# DAC_STM32_Board_v5_-_AD5391.net
KiCad netlist of a schematic drawn in EAGLE
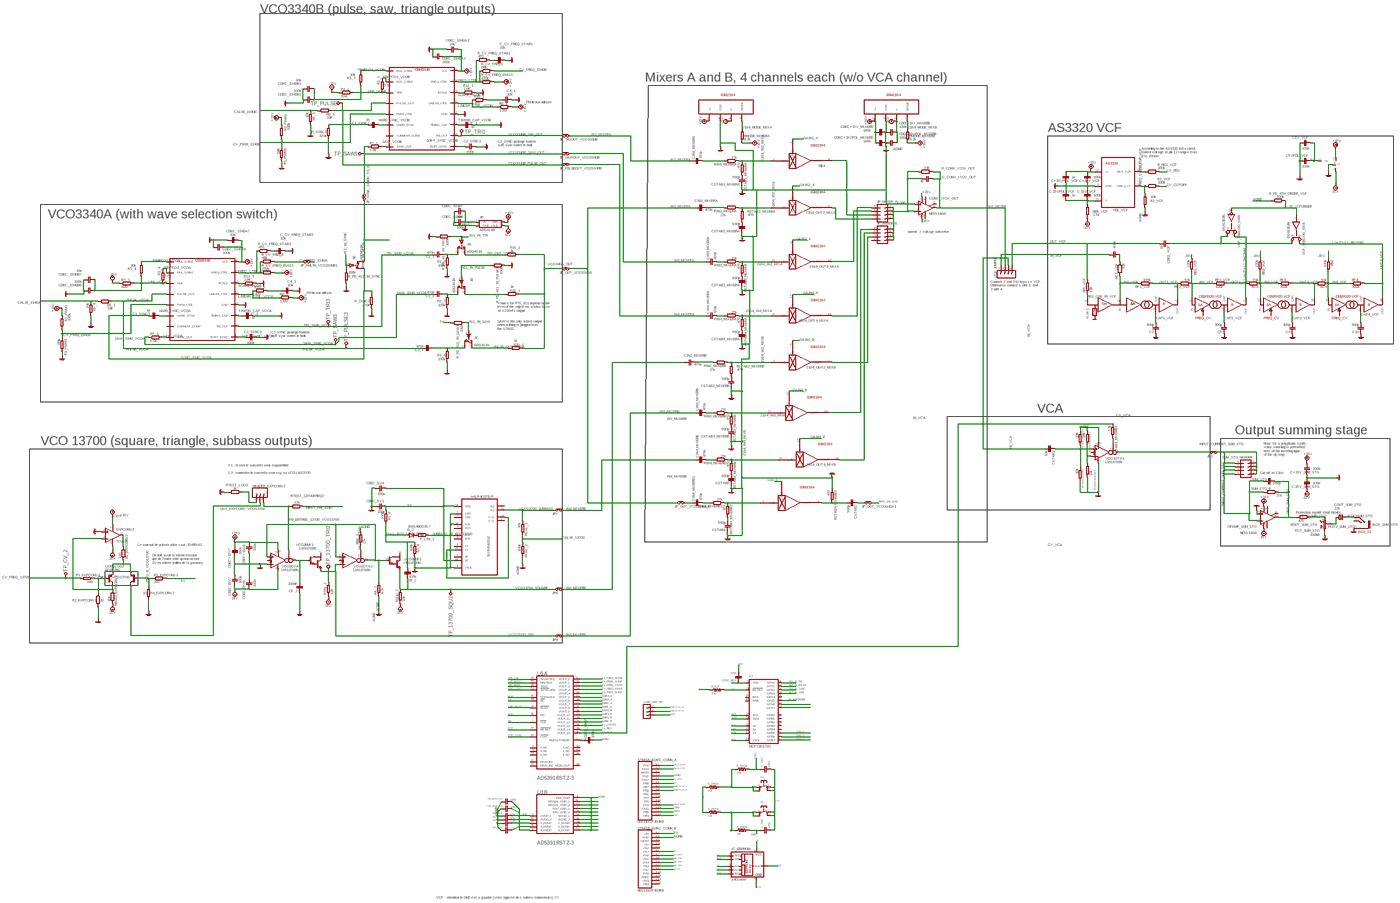
[diagram p0: schematic, sheet 1, overview]
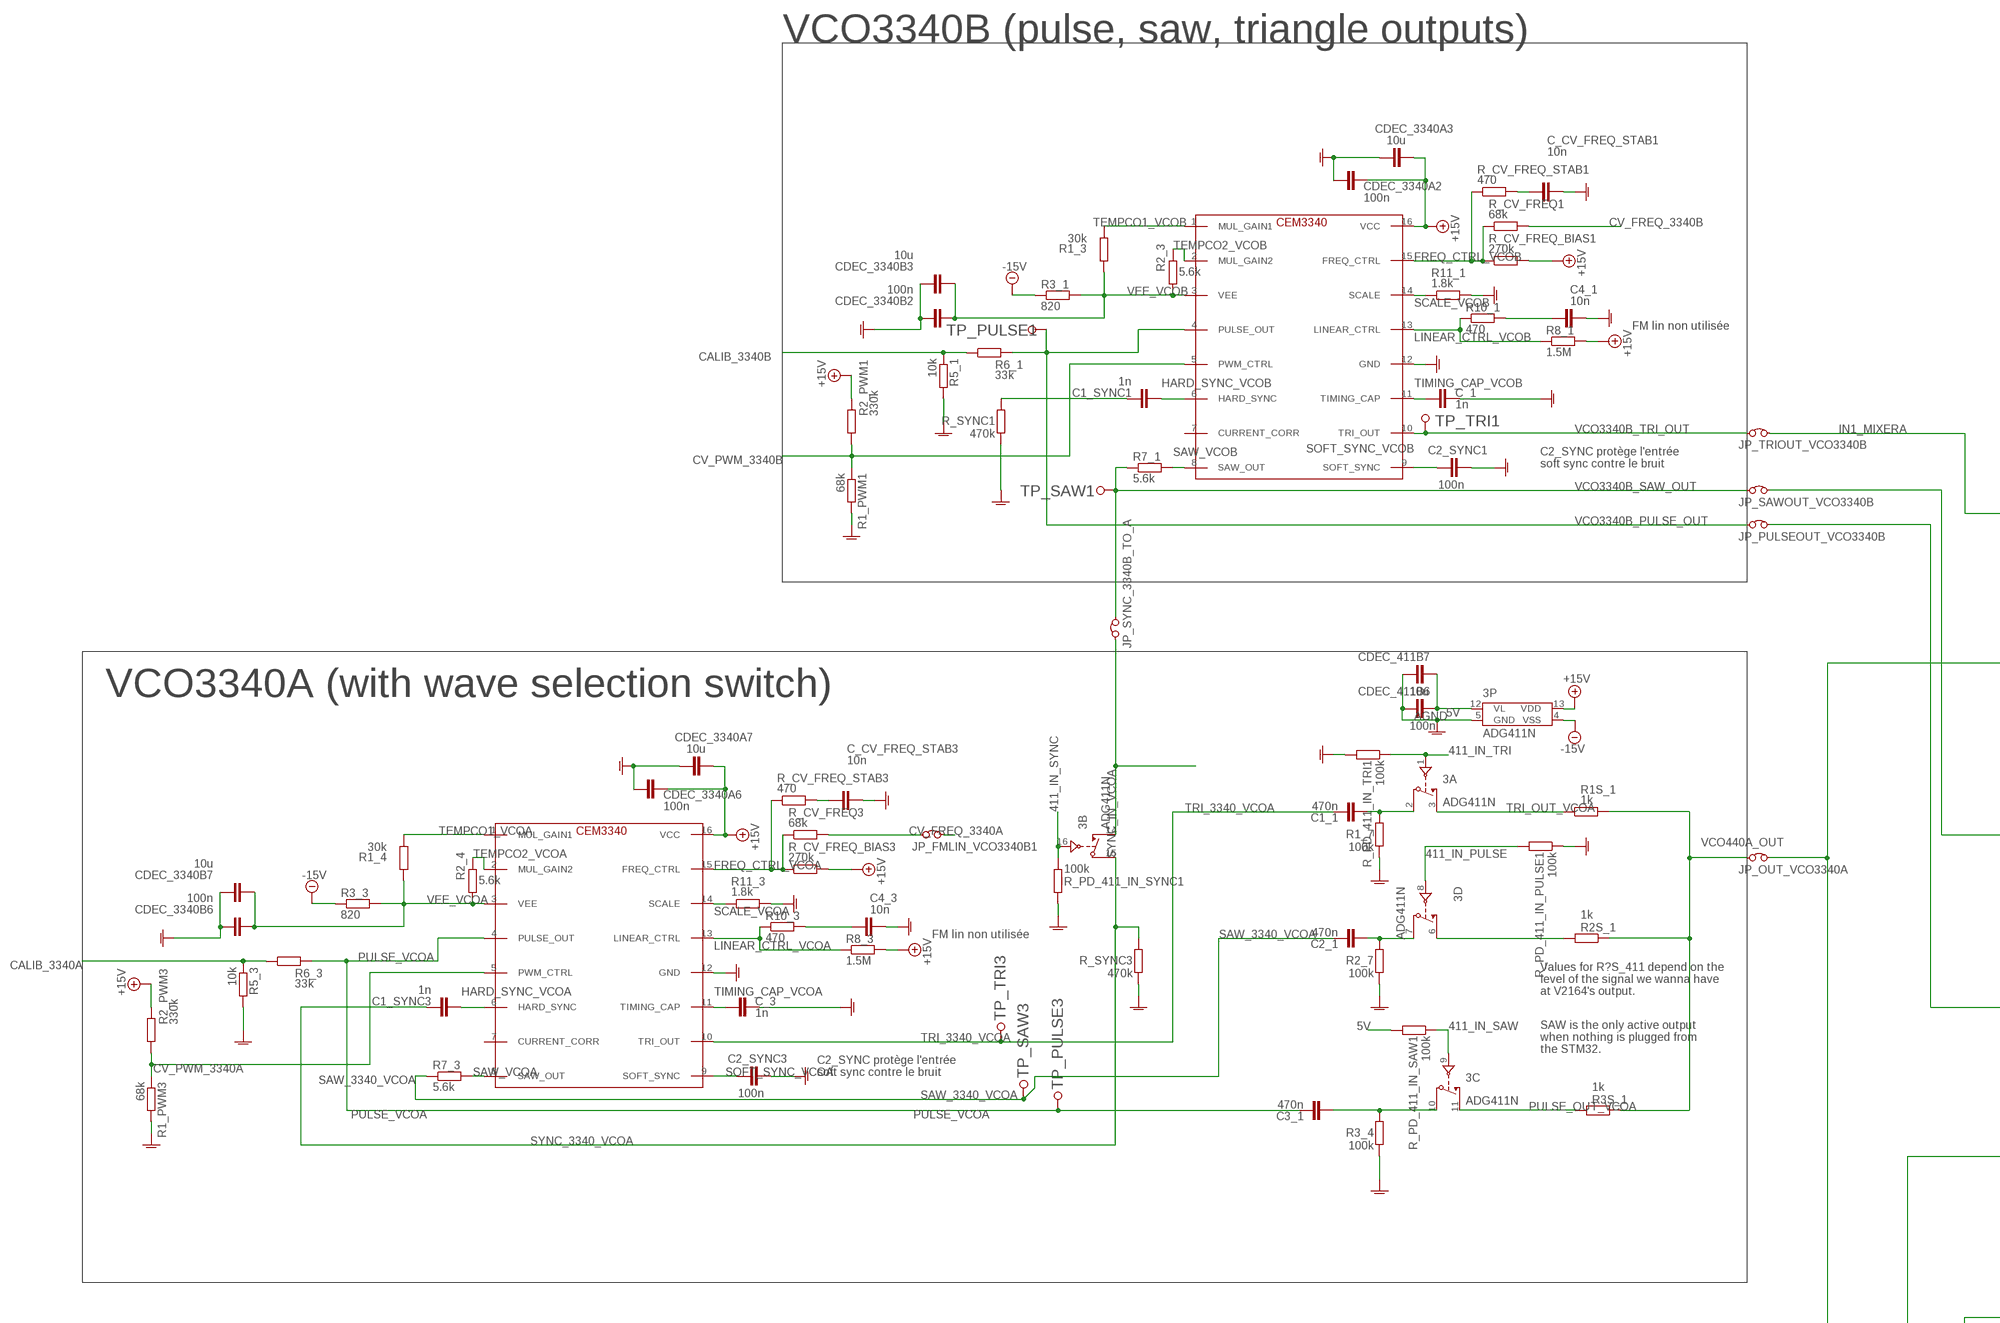
[diagram p1: schematic, sheet 1, part 1 of 5]
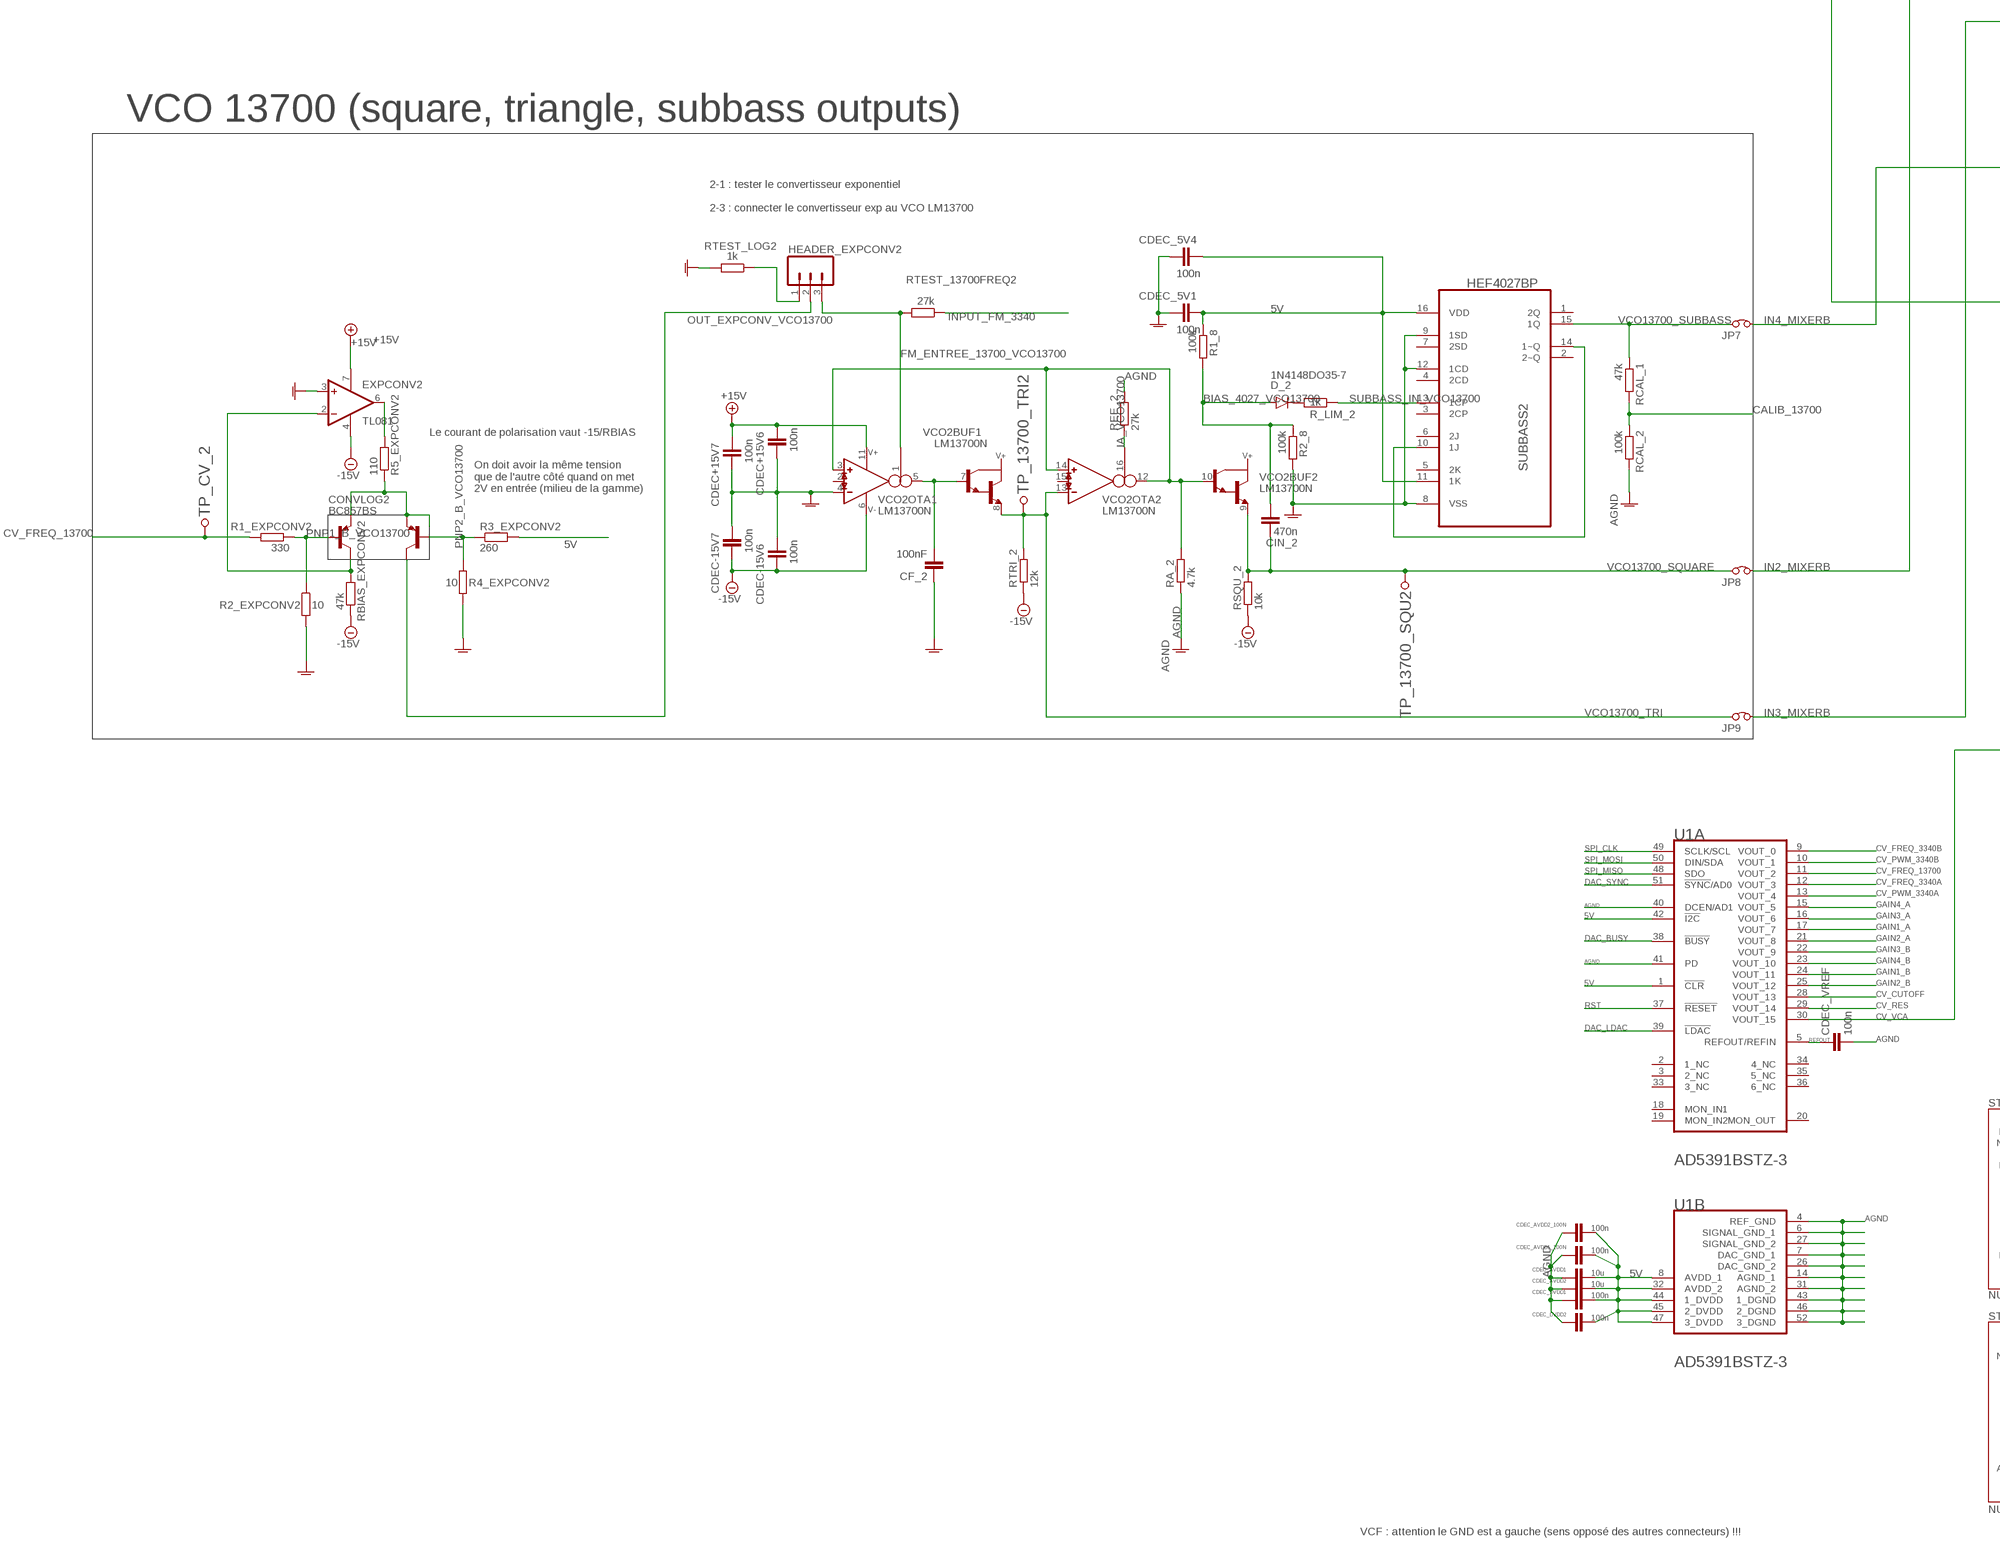
[diagram p2: schematic, sheet 1, part 2 of 5]
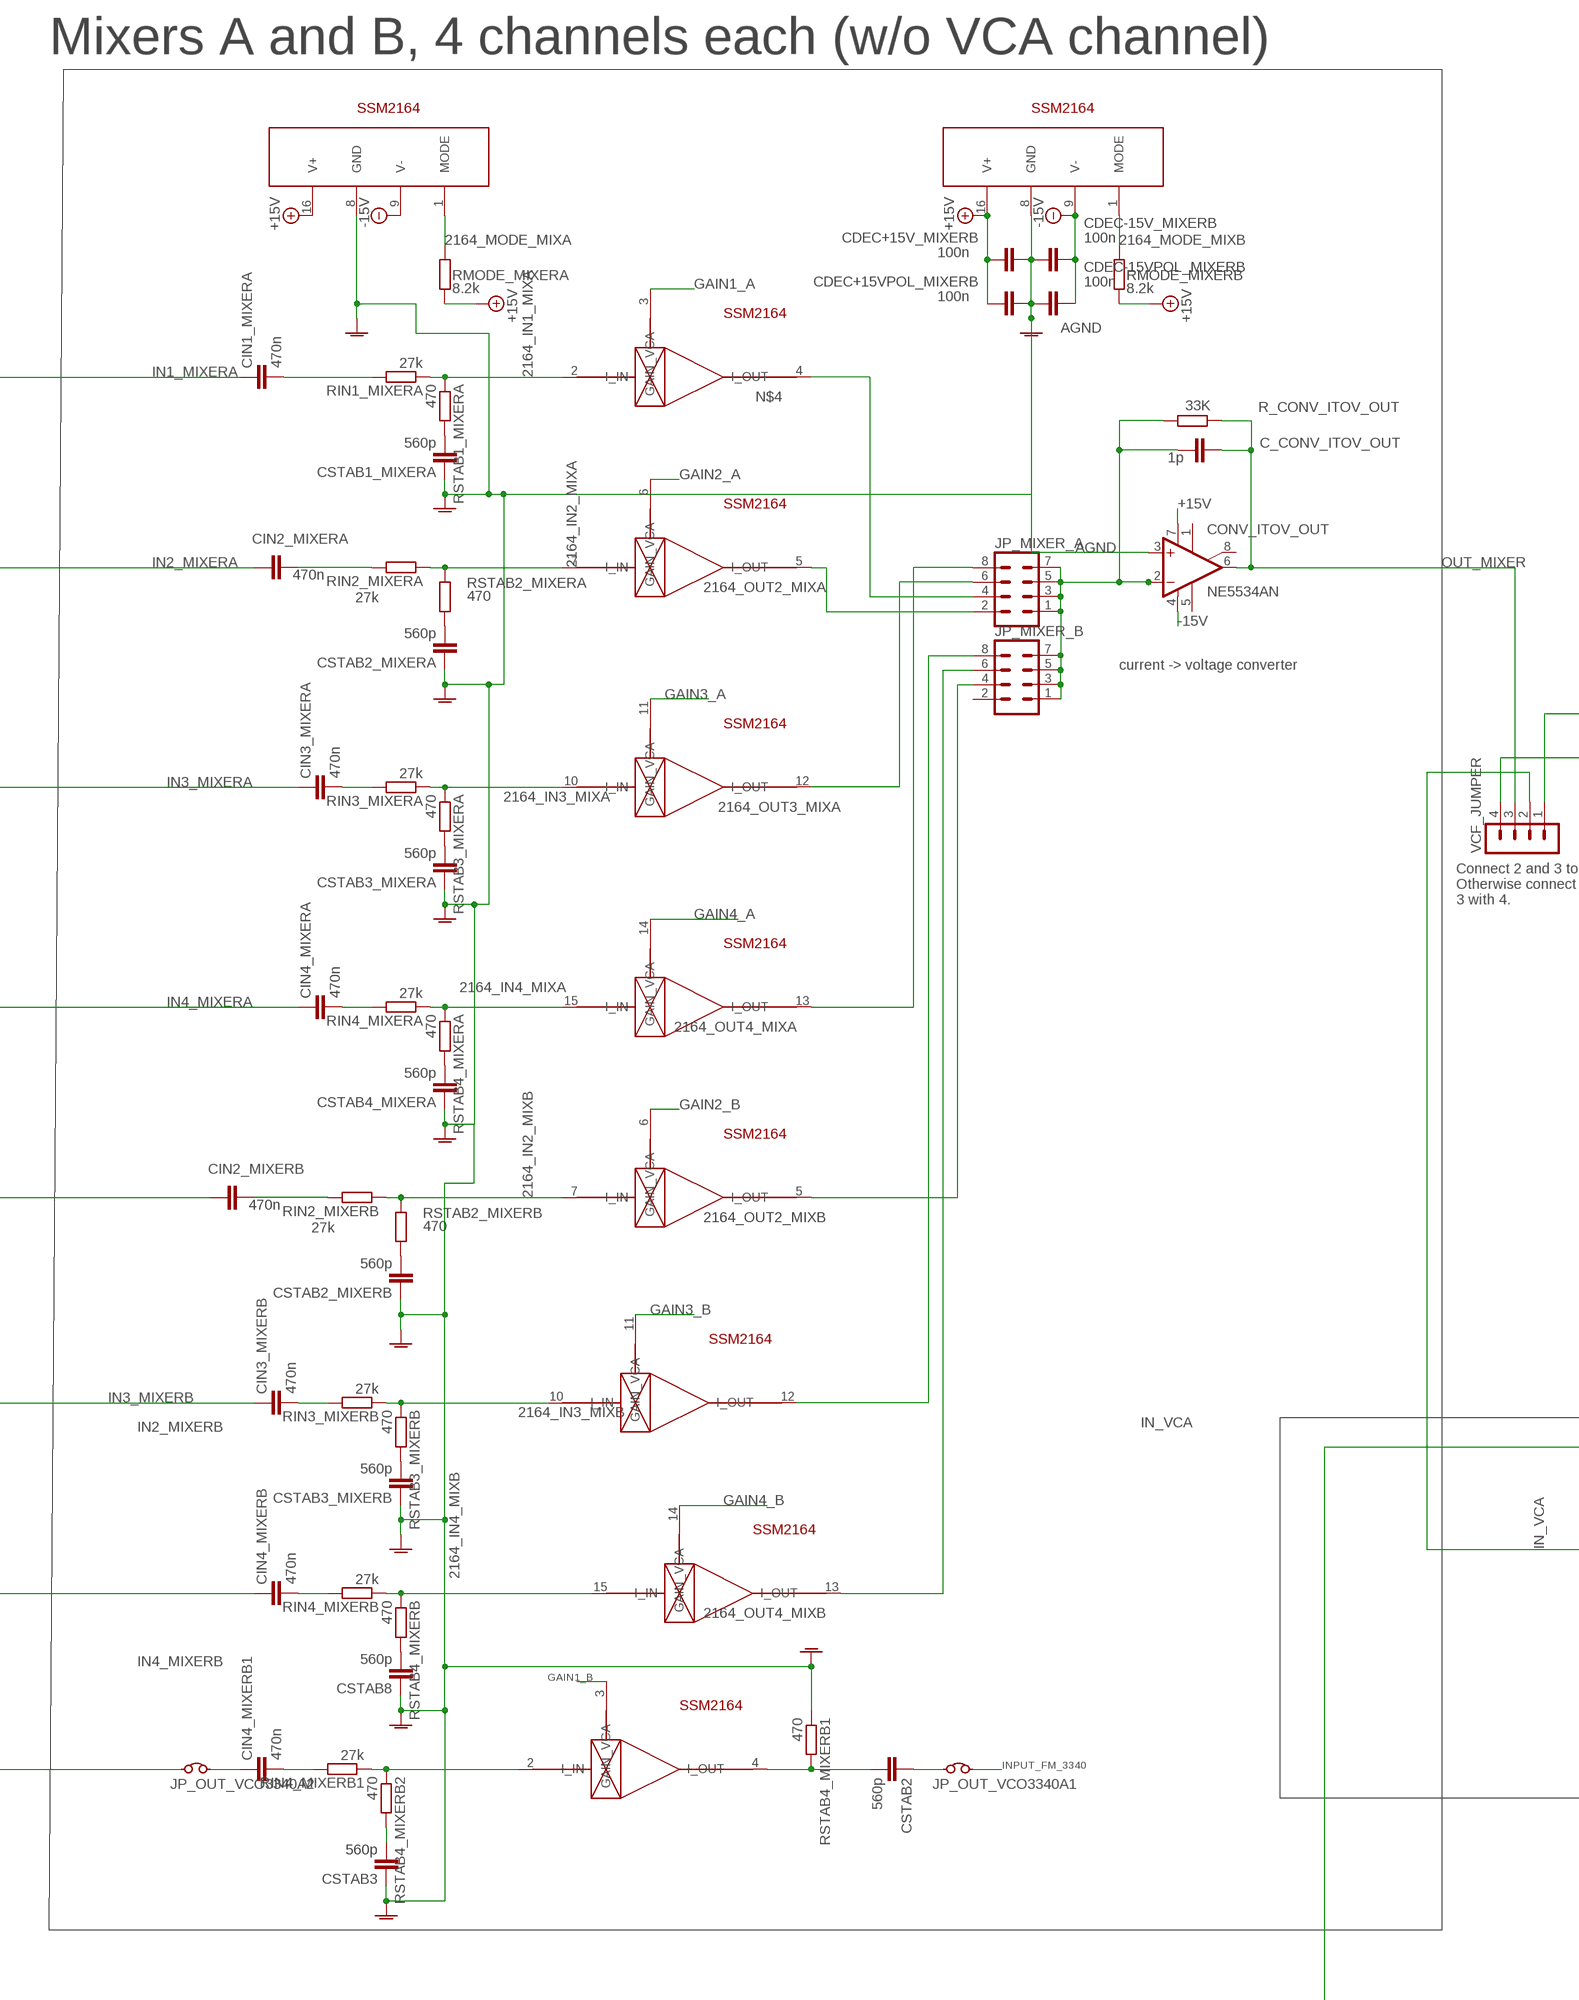
[diagram p3: schematic, sheet 1, part 3 of 5]
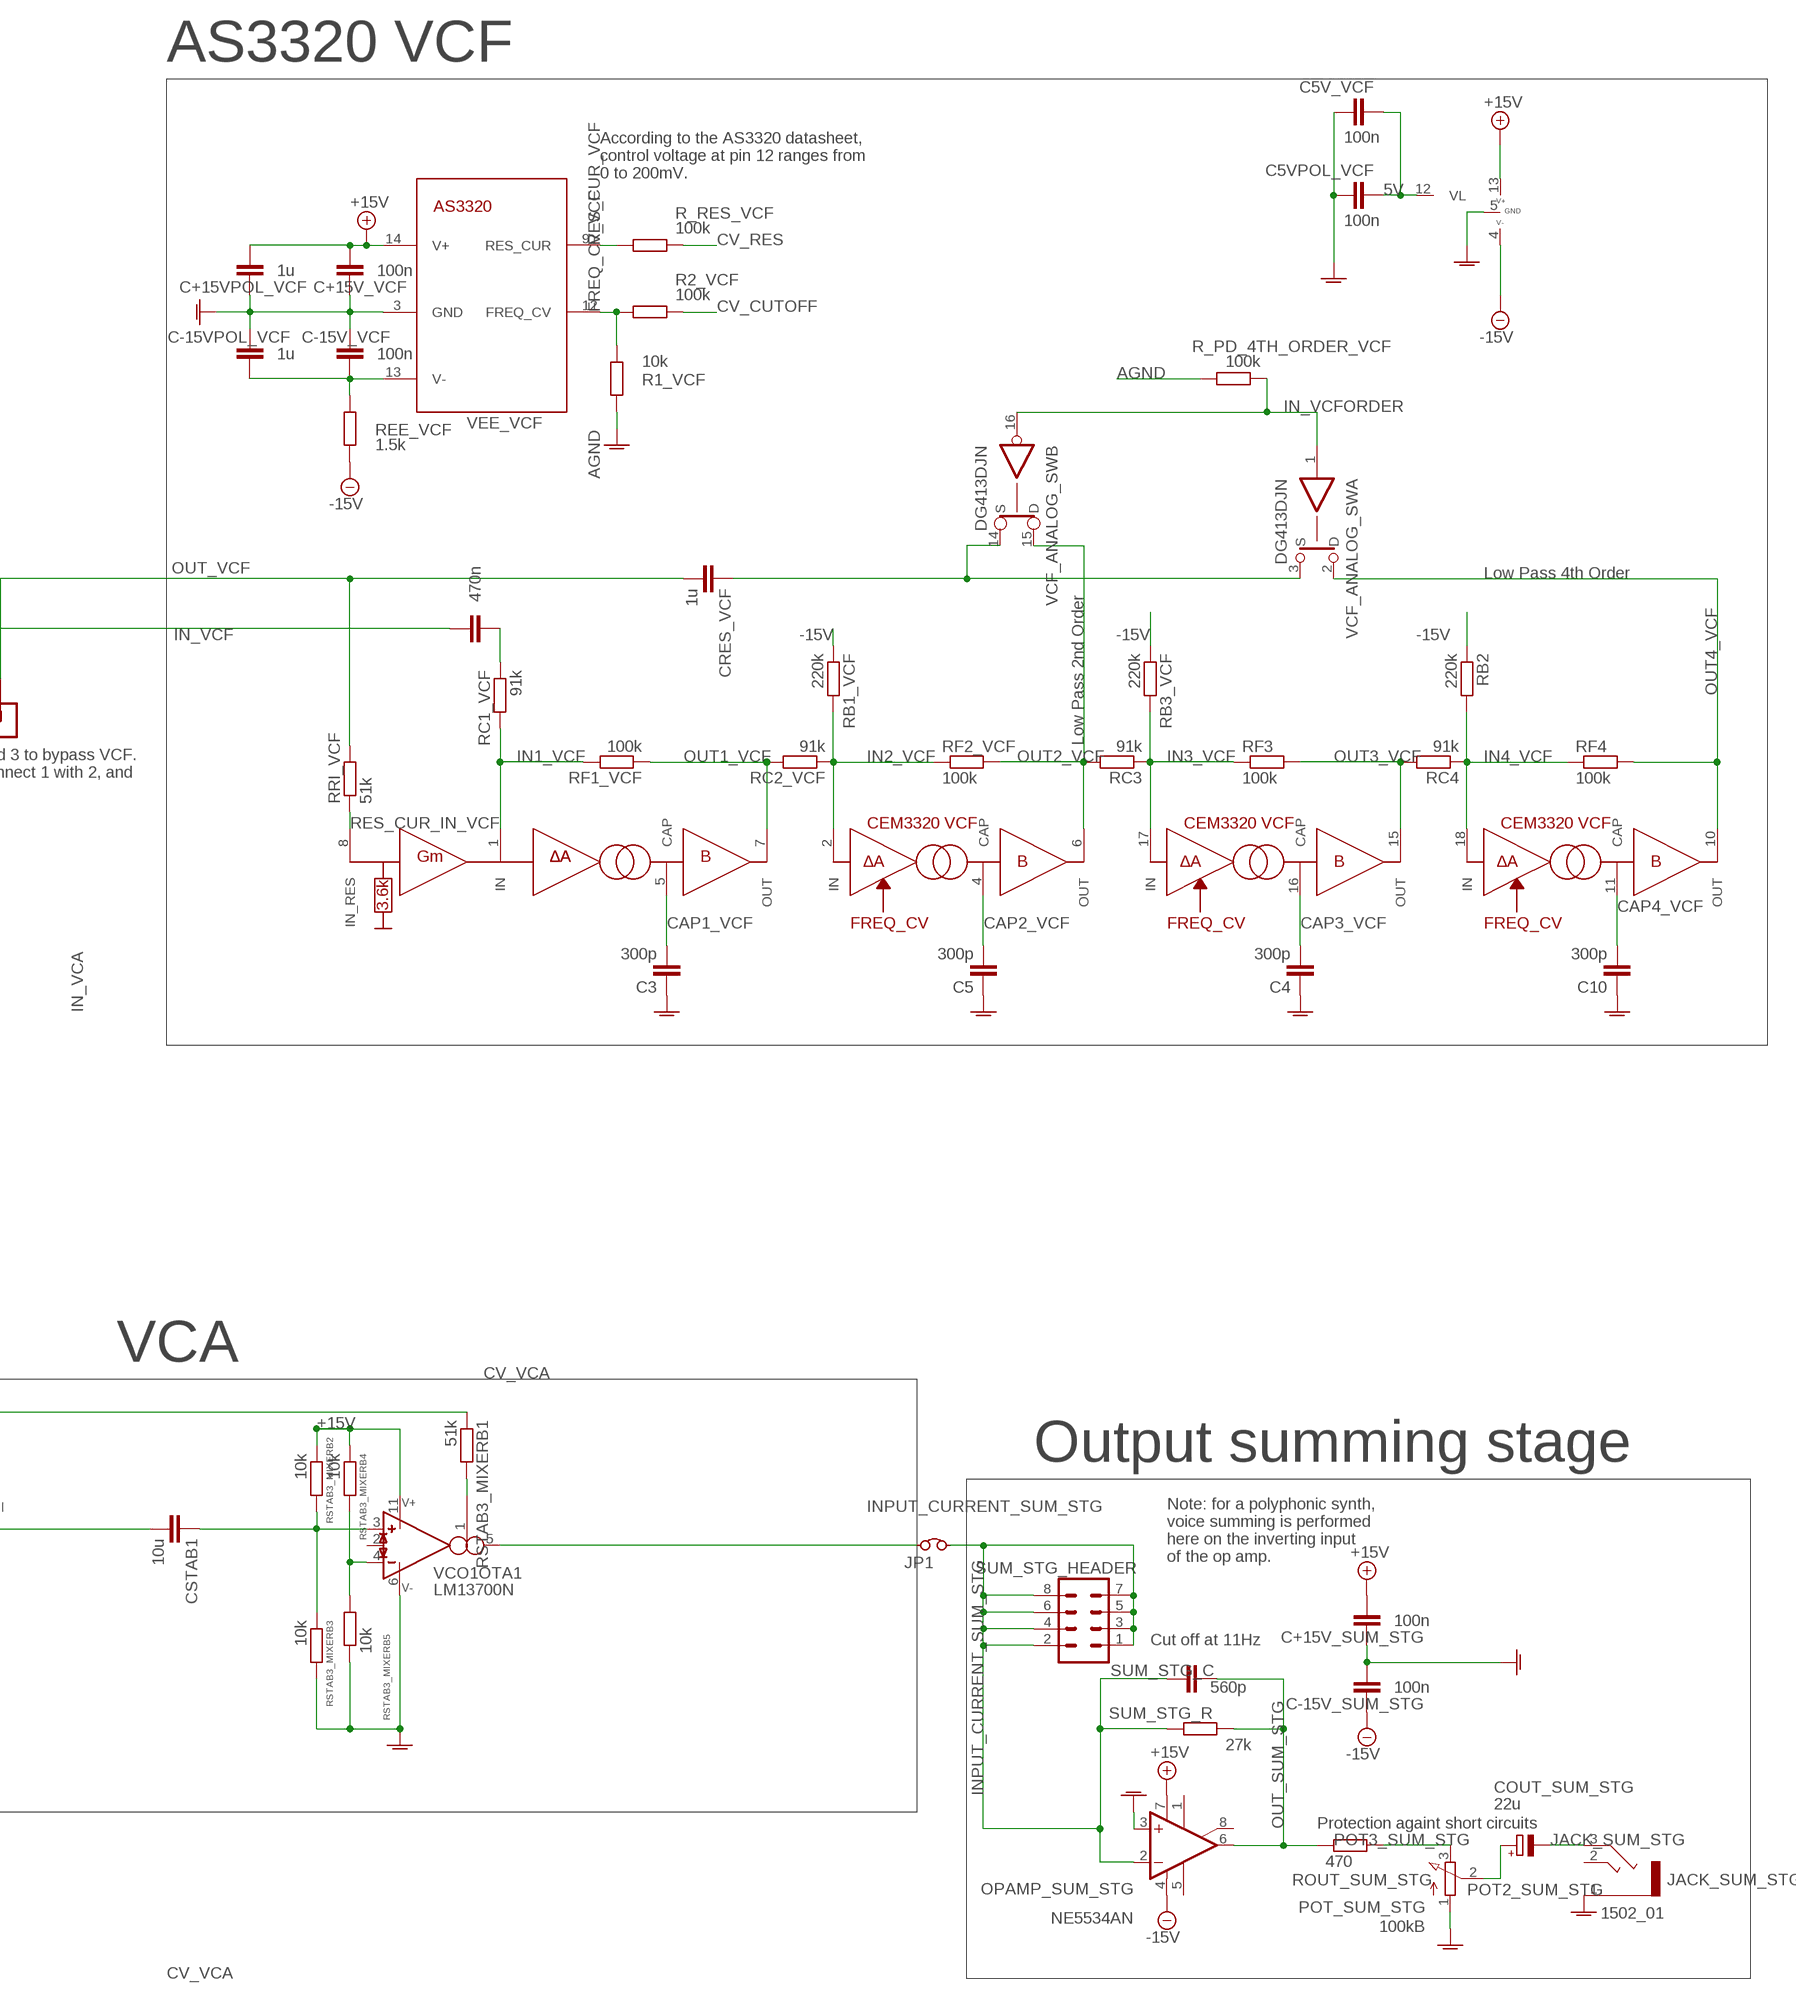
[diagram p4: schematic, sheet 1, part 4 of 5]
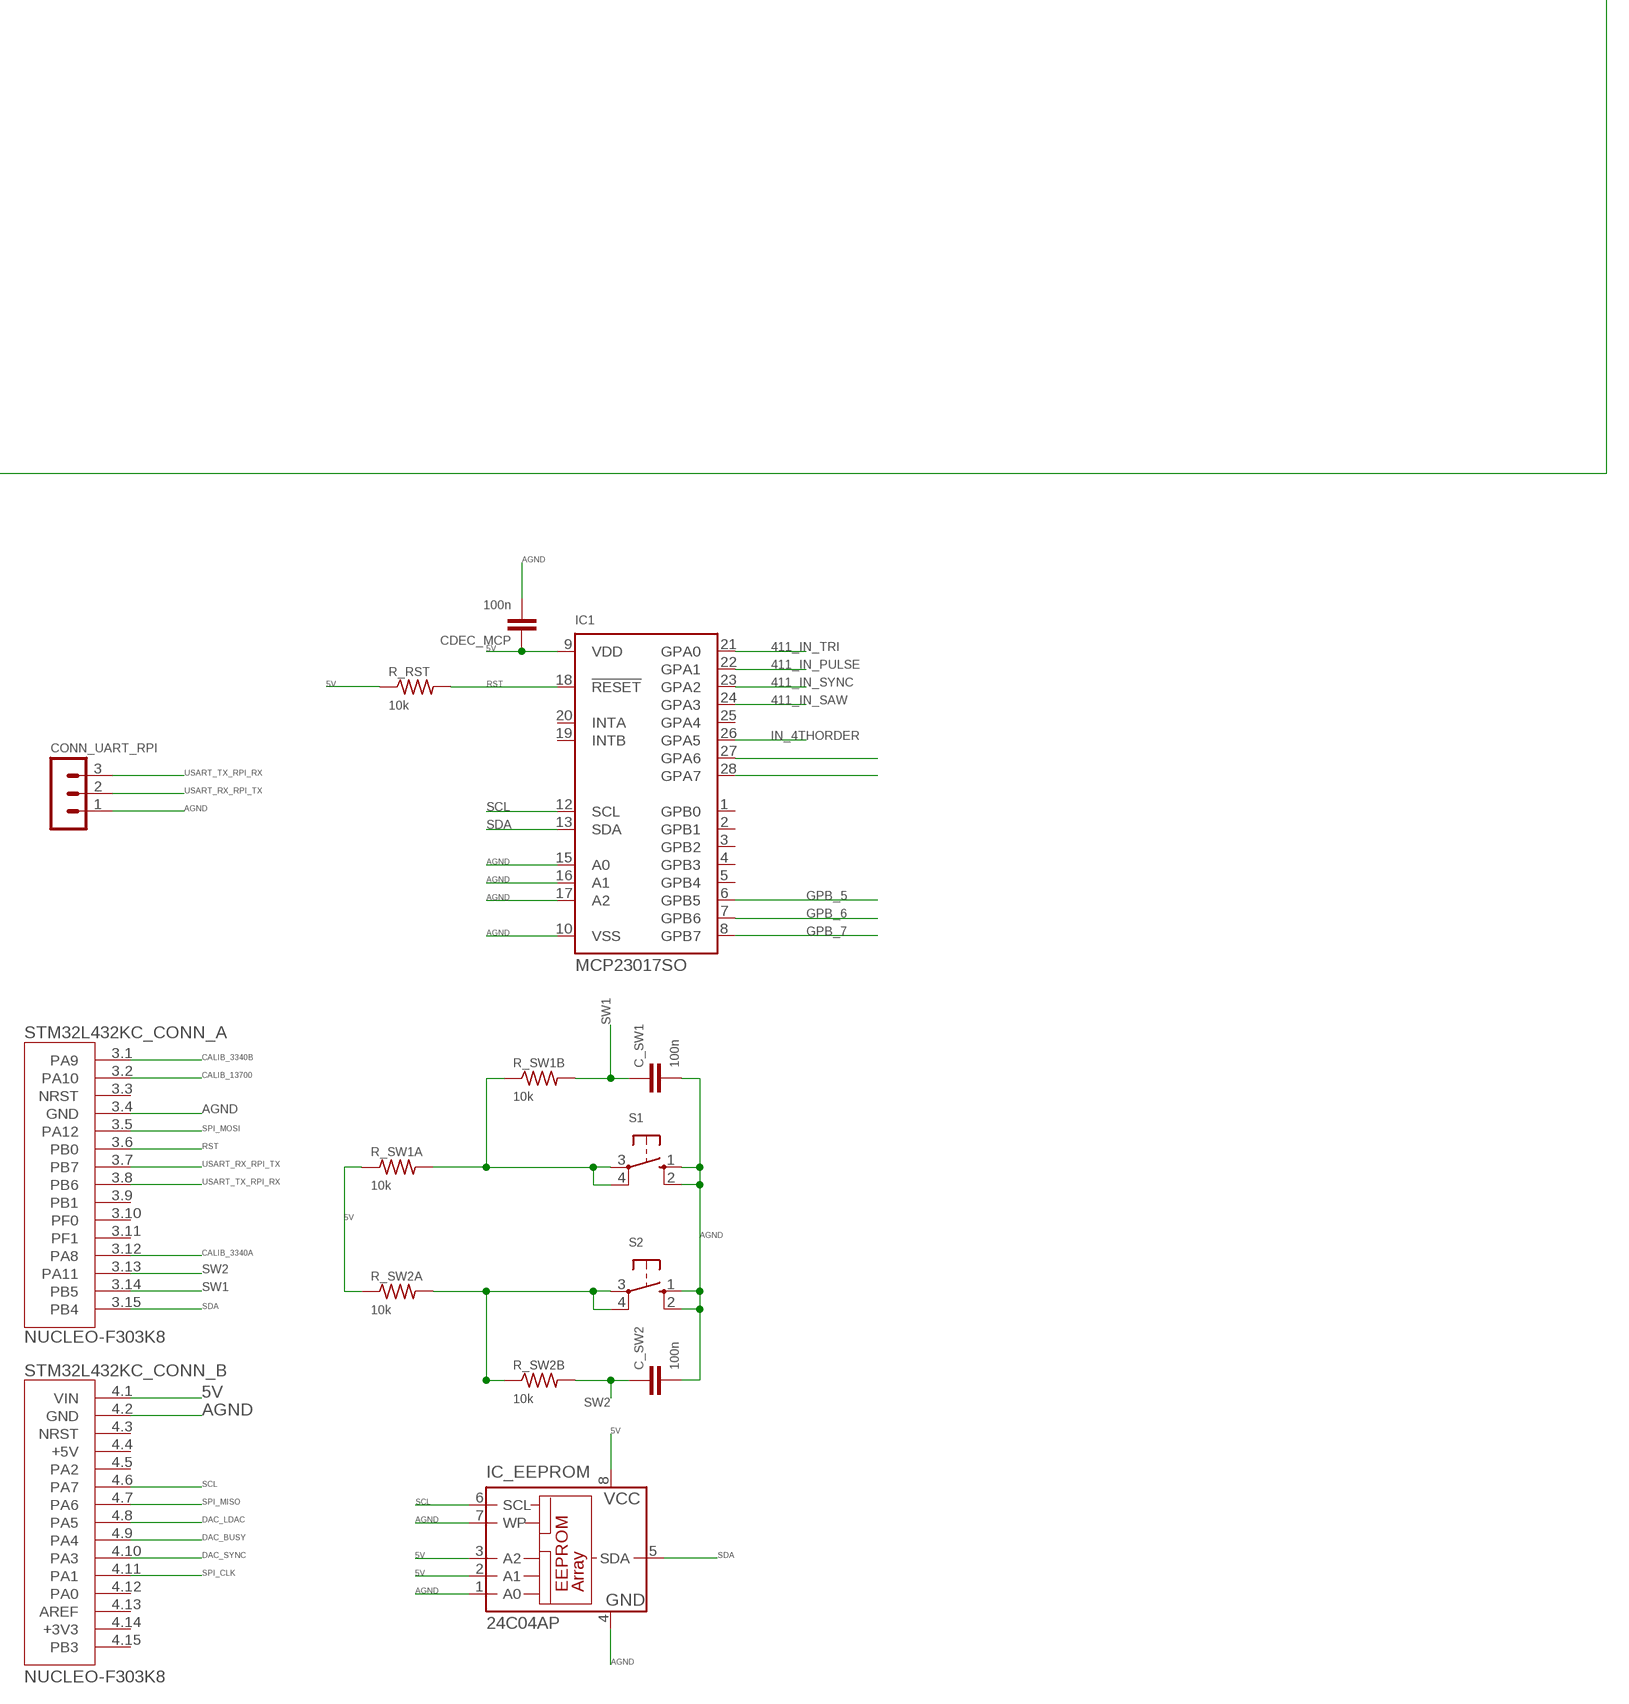
[diagram p5: schematic, sheet 1, part 5 of 5]

(export (version "E")
  (design (tool "Eeschema 10.0.6"))
  (components
    (comp (ref "3")
      (value "ADG411N")
      (footprint "eagle-import:DIL16")
      (fields (field (name "MF") "ALTERA CORPORATION") (field (name "MPN") "ADG411BN"))
      (libsource (lib "eagle-import") (part "ADG411N"))
    )
    (comp (ref "3340A")
      (value "CEM3340")
      (footprint "eagle-import:DIL16")
      (libsource (lib "eagle-import") (part "CEM3340"))
    )
    (comp (ref "3340B")
      (value "CEM3340")
      (footprint "eagle-import:DIL16")
      (libsource (lib "eagle-import") (part "CEM3340"))
    )
    (comp (ref "C+15VPOL_VCF")
      (value "1u")
      (footprint "eagle-import:C075-032X103")
      (libsource (lib "eagle-import") (part "rcl_334_C-EU075-032X103"))
    )
    (comp (ref "C+15V_SUM_STG")
      (value "100n")
      (footprint "eagle-import:C075-032X103")
      (libsource (lib "eagle-import") (part "rcl_334_C-EU075-032X103"))
    )
    (comp (ref "C+15V_VCF")
      (value "100n")
      (footprint "eagle-import:C075-032X103")
      (libsource (lib "eagle-import") (part "rcl_334_C-EU075-032X103"))
    )
    (comp (ref "C-15VPOL_VCF")
      (value "1u")
      (footprint "eagle-import:C075-032X103")
      (libsource (lib "eagle-import") (part "rcl_334_C-EU075-032X103"))
    )
    (comp (ref "C-15V_SUM_STG")
      (value "100n")
      (footprint "eagle-import:C075-032X103")
      (libsource (lib "eagle-import") (part "rcl_334_C-EU075-032X103"))
    )
    (comp (ref "C-15V_VCF")
      (value "100n")
      (footprint "eagle-import:C075-032X103")
      (libsource (lib "eagle-import") (part "rcl_334_C-EU075-032X103"))
    )
    (comp (ref "C1_1")
      (value "470n")
      (footprint "eagle-import:C075-032X103")
      (libsource (lib "eagle-import") (part "rcl_334_C-EU075-032X103"))
    )
    (comp (ref "C1_SYNC1")
      (value "1n")
      (footprint "eagle-import:C075-032X103")
      (libsource (lib "eagle-import") (part "rcl_334_C-EU075-032X103"))
    )
    (comp (ref "C1_SYNC3")
      (value "1n")
      (footprint "eagle-import:C075-032X103")
      (libsource (lib "eagle-import") (part "rcl_334_C-EU075-032X103"))
    )
    (comp (ref "C2_1")
      (value "470n")
      (footprint "eagle-import:C075-032X103")
      (libsource (lib "eagle-import") (part "rcl_334_C-EU075-032X103"))
    )
    (comp (ref "C2_SYNC1")
      (value "100n")
      (footprint "eagle-import:C075-032X103")
      (libsource (lib "eagle-import") (part "rcl_334_C-EU075-032X103"))
    )
    (comp (ref "C2_SYNC3")
      (value "100n")
      (footprint "eagle-import:C050-025X075")
      (libsource (lib "eagle-import") (part "rcl_334_C-EU050-025X075"))
    )
    (comp (ref "C3")
      (value "300p")
      (footprint "eagle-import:C075-032X103")
      (libsource (lib "eagle-import") (part "rcl_334_C-EU075-032X103"))
    )
    (comp (ref "C3_1")
      (value "470n")
      (footprint "eagle-import:C102-043X133")
      (libsource (lib "eagle-import") (part "rcl_334_C-EU102-043X133"))
    )
    (comp (ref "C4")
      (value "300p")
      (footprint "eagle-import:C075-032X103")
      (libsource (lib "eagle-import") (part "rcl_334_C-EU075-032X103"))
    )
    (comp (ref "C4_1")
      (value "10n")
      (footprint "eagle-import:C050-025X075")
      (libsource (lib "eagle-import") (part "rcl_334_C-EU050-025X075"))
    )
    (comp (ref "C4_3")
      (value "10n")
      (footprint "eagle-import:C050-025X075")
      (libsource (lib "eagle-import") (part "rcl_334_C-EU050-025X075"))
    )
    (comp (ref "C5")
      (value "300p")
      (footprint "eagle-import:C075-032X103")
      (libsource (lib "eagle-import") (part "rcl_334_C-EU075-032X103"))
    )
    (comp (ref "C5VPOL_VCF")
      (value "100n")
      (footprint "eagle-import:C075-032X103")
      (libsource (lib "eagle-import") (part "rcl_334_C-EU075-032X103"))
    )
    (comp (ref "C5V_VCF")
      (value "100n")
      (footprint "eagle-import:C075-032X103")
      (libsource (lib "eagle-import") (part "rcl_334_C-EU075-032X103"))
    )
    (comp (ref "C10")
      (value "300p")
      (footprint "eagle-import:C075-032X103")
      (libsource (lib "eagle-import") (part "rcl_334_C-EU075-032X103"))
    )
    (comp (ref "CDEC+15V6")
      (value "100n")
      (footprint "eagle-import:C075-032X103")
      (libsource (lib "eagle-import") (part "rcl_334_C-EU075-032X103"))
    )
    (comp (ref "CDEC+15V7")
      (value "100n")
      (footprint "eagle-import:C050-025X075")
      (libsource (lib "eagle-import") (part "rcl_334_C-EU050-025X075"))
    )
    (comp (ref "CDEC+15VPOL_MIXERB")
      (value "100n")
      (footprint "eagle-import:C075-032X103")
      (libsource (lib "eagle-import") (part "rcl_334_C-EU075-032X103"))
    )
    (comp (ref "CDEC+15V_MIXERB")
      (value "100n")
      (footprint "eagle-import:C050-030X075")
      (libsource (lib "eagle-import") (part "rcl_334_C-EU050-030X075"))
    )
    (comp (ref "CDEC-15V6")
      (value "100n")
      (footprint "eagle-import:C050-025X075")
      (libsource (lib "eagle-import") (part "rcl_334_C-EU050-025X075"))
    )
    (comp (ref "CDEC-15V7")
      (value "100n")
      (footprint "eagle-import:C075-032X103")
      (libsource (lib "eagle-import") (part "rcl_334_C-EU075-032X103"))
    )
    (comp (ref "CDEC-15VPOL_MIXERB")
      (value "100n")
      (footprint "eagle-import:C050-030X075")
      (libsource (lib "eagle-import") (part "rcl_334_C-EU050-030X075"))
    )
    (comp (ref "CDEC-15V_MIXERB")
      (value "100n")
      (footprint "eagle-import:C050-030X075")
      (libsource (lib "eagle-import") (part "rcl_334_C-EU050-030X075"))
    )
    (comp (ref "CDEC_5V1")
      (value "100n")
      (footprint "eagle-import:C050-025X075")
      (libsource (lib "eagle-import") (part "rcl_334_C-EU050-025X075"))
    )
    (comp (ref "CDEC_5V4")
      (value "100n")
      (footprint "eagle-import:C050-025X075")
      (libsource (lib "eagle-import") (part "rcl_334_C-EU050-025X075"))
    )
    (comp (ref "CDEC_411B6")
      (value "100n")
      (footprint "eagle-import:C050-025X075")
      (libsource (lib "eagle-import") (part "rcl_334_C-EU050-025X075"))
    )
    (comp (ref "CDEC_411B7")
      (value "10u")
      (footprint "eagle-import:C050-025X075")
      (libsource (lib "eagle-import") (part "rcl_334_C-EU050-025X075"))
    )
    (comp (ref "CDEC_3340A2")
      (value "100n")
      (footprint "eagle-import:C050-025X075")
      (libsource (lib "eagle-import") (part "rcl_334_C-EU050-025X075"))
    )
    (comp (ref "CDEC_3340A3")
      (value "10u")
      (footprint "eagle-import:C075-032X103")
      (libsource (lib "eagle-import") (part "rcl_334_C-EU075-032X103"))
    )
    (comp (ref "CDEC_3340A6")
      (value "100n")
      (footprint "eagle-import:C050-025X075")
      (libsource (lib "eagle-import") (part "rcl_334_C-EU050-025X075"))
    )
    (comp (ref "CDEC_3340A7")
      (value "10u")
      (footprint "eagle-import:C050-025X075")
      (libsource (lib "eagle-import") (part "rcl_334_C-EU050-025X075"))
    )
    (comp (ref "CDEC_3340B2")
      (value "100n")
      (footprint "eagle-import:C050-025X075")
      (libsource (lib "eagle-import") (part "rcl_334_C-EU050-025X075"))
    )
    (comp (ref "CDEC_3340B3")
      (value "10u")
      (footprint "eagle-import:C050-025X075")
      (libsource (lib "eagle-import") (part "rcl_334_C-EU050-025X075"))
    )
    (comp (ref "CDEC_3340B6")
      (value "100n")
      (footprint "eagle-import:C050-025X075")
      (libsource (lib "eagle-import") (part "rcl_334_C-EU050-025X075"))
    )
    (comp (ref "CDEC_3340B7")
      (value "10u")
      (footprint "eagle-import:C050-025X075")
      (libsource (lib "eagle-import") (part "rcl_334_C-EU050-025X075"))
    )
    (comp (ref "CDEC_AVDD1")
      (value "10u")
      (footprint "eagle-import:C050-030X075")
      (libsource (lib "eagle-import") (part "C-EU050-030X075"))
    )
    (comp (ref "CDEC_AVDD1_100N")
      (value "100n")
      (footprint "eagle-import:C050-030X075")
      (libsource (lib "eagle-import") (part "C-EU050-030X075"))
    )
    (comp (ref "CDEC_AVDD2")
      (value "10u")
      (footprint "eagle-import:C050-030X075")
      (libsource (lib "eagle-import") (part "C-EU050-030X075"))
    )
    (comp (ref "CDEC_AVDD2_100N")
      (value "100n")
      (footprint "eagle-import:C050-030X075")
      (libsource (lib "eagle-import") (part "C-EU050-030X075"))
    )
    (comp (ref "CDEC_DVDD1")
      (value "100n")
      (footprint "eagle-import:C075-032X103")
      (libsource (lib "eagle-import") (part "C-EU075-032X103"))
    )
    (comp (ref "CDEC_DVDD2")
      (value "100n")
      (footprint "eagle-import:C050-030X075")
      (libsource (lib "eagle-import") (part "C-EU050-030X075"))
    )
    (comp (ref "CDEC_MCP")
      (value "100n")
      (footprint "eagle-import:C075-032X103")
      (libsource (lib "eagle-import") (part "C-EU075-032X103"))
    )
    (comp (ref "CDEC_VREF")
      (value "100n")
      (footprint "eagle-import:C050-030X075")
      (libsource (lib "eagle-import") (part "C-EU050-030X075"))
    )
    (comp (ref "CF_2")
      (value "100nF")
      (footprint "eagle-import:C050-025X075")
      (libsource (lib "eagle-import") (part "rcl_334_C-EU050-025X075"))
    )
    (comp (ref "CIN1_MIXERA")
      (value "470n")
      (footprint "eagle-import:C050-030X075")
      (fields (field (name "C3") "0.47 micro"))
      (libsource (lib "eagle-import") (part "rcl_334_C-EU050-030X075"))
    )
    (comp (ref "CIN2_MIXERA")
      (value "470n")
      (footprint "eagle-import:C050-030X075")
      (fields (field (name "C3") "0.47 micro"))
      (libsource (lib "eagle-import") (part "rcl_334_C-EU050-030X075"))
    )
    (comp (ref "CIN2_MIXERB")
      (value "470n")
      (footprint "eagle-import:C050-030X075")
      (fields (field (name "C3") "0.47 micro"))
      (libsource (lib "eagle-import") (part "rcl_334_C-EU050-030X075"))
    )
    (comp (ref "CIN3_MIXERA")
      (value "470n")
      (footprint "eagle-import:C050-030X075")
      (fields (field (name "C3") "0.47 micro"))
      (libsource (lib "eagle-import") (part "rcl_334_C-EU050-030X075"))
    )
    (comp (ref "CIN3_MIXERB")
      (value "470n")
      (footprint "eagle-import:C050-030X075")
      (fields (field (name "C3") "0.47 micro"))
      (libsource (lib "eagle-import") (part "rcl_334_C-EU050-030X075"))
    )
    (comp (ref "CIN4_MIXERA")
      (value "470n")
      (footprint "eagle-import:C050-030X075")
      (fields (field (name "C3") "0.47 micro"))
      (libsource (lib "eagle-import") (part "rcl_334_C-EU050-030X075"))
    )
    (comp (ref "CIN4_MIXERB")
      (value "470n")
      (footprint "eagle-import:C050-030X075")
      (fields (field (name "C3") "0.47 micro"))
      (libsource (lib "eagle-import") (part "rcl_334_C-EU050-030X075"))
    )
    (comp (ref "CIN4_MIXERB1")
      (value "470n")
      (footprint "eagle-import:C050-030X075")
      (fields (field (name "C3") "0.47 micro"))
      (libsource (lib "eagle-import") (part "rcl_334_C-EU050-030X075"))
    )
    (comp (ref "CIN_2")
      (value "470n")
      (footprint "eagle-import:C050-025X075")
      (libsource (lib "eagle-import") (part "rcl_334_C-EU050-025X075"))
    )
    (comp (ref "CONN_UART_RPI")
      (value "MA03-1")
      (footprint "eagle-import:MA03-1")
      (libsource (lib "eagle-import") (part "MA03-1"))
    )
    (comp (ref "CONVLOG2")
      (value "BC857BS")
      (footprint "eagle-import:DIL06")
      (libsource (lib "eagle-import") (part "BC857BS"))
    )
    (comp (ref "CONV_ITOV_OUT")
      (value "NE5534AN")
      (footprint "eagle-import:DIL08")
      (libsource (lib "eagle-import") (part "linear_262_NE5534NA"))
    )
    (comp (ref "COUT_SUM_STG")
      (value "22u")
      (footprint "eagle-import:B45181A")
      (libsource (lib "eagle-import") (part "CPOL-EUB45181A"))
    )
    (comp (ref "CRES_VCF")
      (value "1u")
      (footprint "eagle-import:C075-032X103")
      (libsource (lib "eagle-import") (part "rcl_334_C-EU075-032X103"))
    )
    (comp (ref "CSTAB1")
      (value "10u")
      (footprint "eagle-import:C050-030X075")
      (libsource (lib "eagle-import") (part "rcl_334_C-EU050-030X075"))
    )
    (comp (ref "CSTAB1_MIXERA")
      (value "560p")
      (footprint "eagle-import:C050-030X075")
      (libsource (lib "eagle-import") (part "rcl_334_C-EU050-030X075"))
    )
    (comp (ref "CSTAB2")
      (value "560p")
      (footprint "eagle-import:C050-030X075")
      (libsource (lib "eagle-import") (part "rcl_334_C-EU050-030X075"))
    )
    (comp (ref "CSTAB2_MIXERA")
      (value "560p")
      (footprint "eagle-import:C050-030X075")
      (libsource (lib "eagle-import") (part "rcl_334_C-EU050-030X075"))
    )
    (comp (ref "CSTAB2_MIXERB")
      (value "560p")
      (footprint "eagle-import:C050-030X075")
      (libsource (lib "eagle-import") (part "rcl_334_C-EU050-030X075"))
    )
    (comp (ref "CSTAB3")
      (value "560p")
      (footprint "eagle-import:C050-030X075")
      (libsource (lib "eagle-import") (part "rcl_334_C-EU050-030X075"))
    )
    (comp (ref "CSTAB3_MIXERA")
      (value "560p")
      (footprint "eagle-import:C050-030X075")
      (libsource (lib "eagle-import") (part "rcl_334_C-EU050-030X075"))
    )
    (comp (ref "CSTAB3_MIXERB")
      (value "560p")
      (footprint "eagle-import:C050-030X075")
      (libsource (lib "eagle-import") (part "rcl_334_C-EU050-030X075"))
    )
    (comp (ref "CSTAB4_MIXERA")
      (value "560p")
      (footprint "eagle-import:C050-030X075")
      (libsource (lib "eagle-import") (part "rcl_334_C-EU050-030X075"))
    )
    (comp (ref "CSTAB8")
      (value "560p")
      (footprint "eagle-import:C050-030X075")
      (libsource (lib "eagle-import") (part "rcl_334_C-EU050-030X075"))
    )
    (comp (ref "C_1")
      (value "1n")
      (footprint "eagle-import:C050-025X075")
      (libsource (lib "eagle-import") (part "rcl_334_C-EU050-025X075"))
    )
    (comp (ref "C_3")
      (value "1n")
      (footprint "eagle-import:C050-025X075")
      (libsource (lib "eagle-import") (part "rcl_334_C-EU050-025X075"))
    )
    (comp (ref "C_CONV_ITOV_OUT")
      (value "1p")
      (footprint "eagle-import:C050-030X075")
      (fields (field (name "C3") "0.47 micro"))
      (libsource (lib "eagle-import") (part "rcl_334_C-EU050-030X075"))
    )
    (comp (ref "C_CV_FREQ_STAB1")
      (value "10n")
      (footprint "eagle-import:C075-032X103")
      (libsource (lib "eagle-import") (part "rcl_334_C-EU075-032X103"))
    )
    (comp (ref "C_CV_FREQ_STAB3")
      (value "10n")
      (footprint "eagle-import:C075-032X103")
      (libsource (lib "eagle-import") (part "rcl_334_C-EU075-032X103"))
    )
    (comp (ref "C_IN2")
      (value "470n")
      (footprint "eagle-import:C050-025X075")
      (libsource (lib "eagle-import") (part "rcl_334_C-EU050-025X075"))
    )
    (comp (ref "C_SW1")
      (value "100n")
      (footprint "eagle-import:C050-030X075")
      (libsource (lib "eagle-import") (part "C-EU050-030X075"))
    )
    (comp (ref "C_SW2")
      (value "100n")
      (footprint "eagle-import:C050-030X075")
      (libsource (lib "eagle-import") (part "C-EU050-030X075"))
    )
    (comp (ref "D_2")
      (value "1N4148DO35-7")
      (footprint "eagle-import:DO35-7")
      (libsource (lib "eagle-import") (part "1N4148DO35-7"))
    )
    (comp (ref "EXPCONV2")
      (value "TL081")
      (footprint "eagle-import:DIL08")
      (libsource (lib "eagle-import") (part "1AMP_P7+4N"))
    )
    (comp (ref "HEADER_EXPCONV2")
      (value "M03")
      (footprint "eagle-import:03P")
      (libsource (lib "eagle-import") (part "M03"))
    )
    (comp (ref "IC1")
      (value "MCP23017SO")
      (footprint "eagle-import:SO28W")
      (fields (field (name "MF") "MICROCHIP") (field (name "MPN") "MCP23017-E/SO"))
      (libsource (lib "eagle-import") (part "MCP23017SO"))
    )
    (comp (ref "IC_EEPROM")
      (value "24C04AP")
      (footprint "eagle-import:DIL8")
      (fields (field (name "MPN") "AT24C04B-PU"))
      (libsource (lib "eagle-import") (part "24CP04A"))
    )
    (comp (ref "JACK_SUM_STG")
      (value "1502_01")
      (footprint "eagle-import:1502_01")
      (libsource (lib "eagle-import") (part "1502_01"))
    )
    (comp (ref "JP1")
      (value "JUMPER")
      (footprint "eagle-import:HDR2X1")
      (libsource (lib "eagle-import") (part "JUMPER"))
    )
    (comp (ref "JP7")
      (value "JUMPER")
      (footprint "eagle-import:HDR2X1")
      (libsource (lib "eagle-import") (part "JUMPER"))
    )
    (comp (ref "JP8")
      (value "JUMPER")
      (footprint "eagle-import:HDR2X1")
      (libsource (lib "eagle-import") (part "JUMPER"))
    )
    (comp (ref "JP9")
      (value "JUMPER")
      (footprint "eagle-import:HDR2X1")
      (libsource (lib "eagle-import") (part "JUMPER"))
    )
    (comp (ref "JP_FMLIN_VCO3340B1")
      (value "JUMPER")
      (footprint "eagle-import:HDR2X1")
      (libsource (lib "eagle-import") (part "JUMPER"))
    )
    (comp (ref "JP_MIXER_A")
      (value "MA04-2")
      (footprint "eagle-import:MA04-2")
      (libsource (lib "eagle-import") (part "MA04-2"))
    )
    (comp (ref "JP_MIXER_B")
      (value "MA04-2")
      (footprint "eagle-import:MA04-2")
      (libsource (lib "eagle-import") (part "MA04-2"))
    )
    (comp (ref "JP_OUT_VCO3340A")
      (value "JUMPER")
      (footprint "eagle-import:HDR2X1")
      (libsource (lib "eagle-import") (part "JUMPER"))
    )
    (comp (ref "JP_OUT_VCO3340A1")
      (value "JUMPER")
      (footprint "eagle-import:HDR2X1")
      (libsource (lib "eagle-import") (part "JUMPER"))
    )
    (comp (ref "JP_OUT_VCO3340A2")
      (value "JUMPER")
      (footprint "eagle-import:HDR2X1")
      (libsource (lib "eagle-import") (part "JUMPER"))
    )
    (comp (ref "JP_PULSEOUT_VCO3340B")
      (value "JUMPER")
      (footprint "eagle-import:HDR2X1")
      (libsource (lib "eagle-import") (part "JUMPER"))
    )
    (comp (ref "JP_SAWOUT_VCO3340B")
      (value "JUMPER")
      (footprint "eagle-import:HDR2X1")
      (libsource (lib "eagle-import") (part "JUMPER"))
    )
    (comp (ref "JP_SYNC_3340B_TO_A")
      (value "JUMPER")
      (footprint "eagle-import:HDR2X1")
      (libsource (lib "eagle-import") (part "JUMPER"))
    )
    (comp (ref "JP_TRIOUT_VCO3340B")
      (value "JUMPER")
      (footprint "eagle-import:HDR2X1")
      (libsource (lib "eagle-import") (part "JUMPER"))
    )
    (comp (ref "MIXER_A")
      (value "SSM2164_MULTI")
      (footprint "eagle-import:DIL16")
      (libsource (lib "eagle-import") (part "SSM2164_MULTI"))
    )
    (comp (ref "MIXER_B")
      (value "SSM2164_MULTI")
      (footprint "eagle-import:DIL16")
      (libsource (lib "eagle-import") (part "SSM2164_MULTI"))
    )
    (comp (ref "OPAMP_SUM_STG")
      (value "NE5534AN")
      (footprint "eagle-import:DIL08")
      (libsource (lib "eagle-import") (part "NE5534NA"))
    )
    (comp (ref "POT_SUM_STG")
      (value "100kB")
      (footprint "eagle-import:3RP_1610N")
      (libsource (lib "eagle-import") (part "3RP/1610N"))
    )
    (comp (ref "R1S_1")
      (value "1k")
      (footprint "eagle-import:0204_7")
      (libsource (lib "eagle-import") (part "R-EU_0204/7"))
    )
    (comp (ref "R1_3")
      (value "30k")
      (footprint "eagle-import:0204_7")
      (libsource (lib "eagle-import") (part "R-EU_0204/7"))
    )
    (comp (ref "R1_4")
      (value "30k")
      (footprint "eagle-import:0204_7")
      (libsource (lib "eagle-import") (part "R-EU_0204/7"))
    )
    (comp (ref "R1_7")
      (value "100k")
      (footprint "eagle-import:0204_7")
      (libsource (lib "eagle-import") (part "R-EU_0204/7"))
    )
    (comp (ref "R1_8")
      (value "100k")
      (footprint "eagle-import:0204_7")
      (libsource (lib "eagle-import") (part "R-EU_0204/7"))
    )
    (comp (ref "R1_EXPCONV2")
      (value "330")
      (footprint "eagle-import:0204_7")
      (libsource (lib "eagle-import") (part "R-EU_0204/7"))
    )
    (comp (ref "R1_PWM1")
      (value "68k")
      (footprint "eagle-import:0204_7")
      (libsource (lib "eagle-import") (part "R-EU_0204/7"))
    )
    (comp (ref "R1_PWM3")
      (value "68k")
      (footprint "eagle-import:0207_10")
      (libsource (lib "eagle-import") (part "R-EU_0207/10"))
    )
    (comp (ref "R1_VCF")
      (value "10k")
      (footprint "eagle-import:0204_7")
      (libsource (lib "eagle-import") (part "R-EU_0204/7"))
    )
    (comp (ref "R2S_1")
      (value "1k")
      (footprint "eagle-import:0204_7")
      (libsource (lib "eagle-import") (part "R-EU_0204/7"))
    )
    (comp (ref "R2_3")
      (value "5.6k")
      (footprint "eagle-import:0204_7")
      (libsource (lib "eagle-import") (part "R-EU_0204/7"))
    )
    (comp (ref "R2_4")
      (value "5.6k")
      (footprint "eagle-import:0204_7")
      (libsource (lib "eagle-import") (part "R-EU_0204/7"))
    )
    (comp (ref "R2_7")
      (value "100k")
      (footprint "eagle-import:0207_10")
      (libsource (lib "eagle-import") (part "R-EU_0207/10"))
    )
    (comp (ref "R2_8")
      (value "100k")
      (footprint "eagle-import:0204_7")
      (libsource (lib "eagle-import") (part "R-EU_0204/7"))
    )
    (comp (ref "R2_EXPCONV2")
      (value "10")
      (footprint "eagle-import:0204_7")
      (libsource (lib "eagle-import") (part "R-EU_0204/7"))
    )
    (comp (ref "R2_PWM1")
      (value "330k")
      (footprint "eagle-import:0204_7")
      (libsource (lib "eagle-import") (part "R-EU_0204/7"))
    )
    (comp (ref "R2_PWM3")
      (value "330k")
      (footprint "eagle-import:0204_7")
      (libsource (lib "eagle-import") (part "R-EU_0204/7"))
    )
    (comp (ref "R2_VCF")
      (value "100k")
      (footprint "eagle-import:0204_7")
      (libsource (lib "eagle-import") (part "R-EU_0204/7"))
    )
    (comp (ref "R3S_1")
      (value "1k")
      (footprint "eagle-import:0207_10")
      (libsource (lib "eagle-import") (part "R-EU_0207/10"))
    )
    (comp (ref "R3_1")
      (value "820")
      (footprint "eagle-import:0204_7")
      (libsource (lib "eagle-import") (part "R-EU_0204/7"))
    )
    (comp (ref "R3_3")
      (value "820")
      (footprint "eagle-import:0204_7")
      (libsource (lib "eagle-import") (part "R-EU_0204/7"))
    )
    (comp (ref "R3_4")
      (value "100k")
      (footprint "eagle-import:0207_10")
      (libsource (lib "eagle-import") (part "R-EU_0207/10"))
    )
    (comp (ref "R3_EXPCONV2")
      (value "260")
      (footprint "eagle-import:0204_7")
      (libsource (lib "eagle-import") (part "R-EU_0204/7"))
    )
    (comp (ref "R4_EXPCONV2")
      (value "10")
      (footprint "eagle-import:0204_7")
      (libsource (lib "eagle-import") (part "R-EU_0204/7"))
    )
    (comp (ref "R5_1")
      (value "10k")
      (footprint "eagle-import:0204_7")
      (libsource (lib "eagle-import") (part "R-EU_0204/7"))
    )
    (comp (ref "R5_3")
      (value "10k")
      (footprint "eagle-import:0204_7")
      (libsource (lib "eagle-import") (part "R-EU_0204/7"))
    )
    (comp (ref "R5_EXPCONV2")
      (value "110")
      (footprint "eagle-import:0204_7")
      (libsource (lib "eagle-import") (part "R-EU_0204/7"))
    )
    (comp (ref "R6_1")
      (value "33k")
      (footprint "eagle-import:0204_7")
      (libsource (lib "eagle-import") (part "R-EU_0204/7"))
    )
    (comp (ref "R6_3")
      (value "33k")
      (footprint "eagle-import:0204_7")
      (libsource (lib "eagle-import") (part "R-EU_0204/7"))
    )
    (comp (ref "R7_1")
      (value "5.6k")
      (footprint "eagle-import:0207_10")
      (libsource (lib "eagle-import") (part "R-EU_0207/10"))
    )
    (comp (ref "R7_3")
      (value "5.6k")
      (footprint "eagle-import:0207_10")
      (libsource (lib "eagle-import") (part "R-EU_0207/10"))
    )
    (comp (ref "R8_1")
      (value "1.5M")
      (footprint "eagle-import:0204_7")
      (libsource (lib "eagle-import") (part "R-EU_0204/7"))
    )
    (comp (ref "R8_3")
      (value "1.5M")
      (footprint "eagle-import:0204_7")
      (libsource (lib "eagle-import") (part "R-EU_0204/7"))
    )
    (comp (ref "R10_1")
      (value "470")
      (footprint "eagle-import:0204_7")
      (libsource (lib "eagle-import") (part "R-EU_0204/7"))
    )
    (comp (ref "R10_3")
      (value "470")
      (footprint "eagle-import:0204_7")
      (libsource (lib "eagle-import") (part "R-EU_0204/7"))
    )
    (comp (ref "R11_1")
      (value "1.8k")
      (footprint "eagle-import:0204_7")
      (libsource (lib "eagle-import") (part "R-EU_0204/7"))
    )
    (comp (ref "R11_3")
      (value "1.8k")
      (footprint "eagle-import:0204_7")
      (libsource (lib "eagle-import") (part "R-EU_0204/7"))
    )
    (comp (ref "RA_2")
      (value "4.7k")
      (footprint "eagle-import:0204_7")
      (libsource (lib "eagle-import") (part "R-EU_0204/7"))
    )
    (comp (ref "RB1_VCF")
      (value "220k")
      (footprint "eagle-import:0204_7")
      (libsource (lib "eagle-import") (part "R-EU_0204/7"))
    )
    (comp (ref "RB2")
      (value "220k")
      (footprint "eagle-import:0204_7")
      (libsource (lib "eagle-import") (part "R-EU_0204/7"))
    )
    (comp (ref "RB3_VCF")
      (value "220k")
      (footprint "eagle-import:0204_7")
      (libsource (lib "eagle-import") (part "R-EU_0204/7"))
    )
    (comp (ref "RBIAS_EXPCONV2")
      (value "47k")
      (footprint "eagle-import:0204_7")
      (libsource (lib "eagle-import") (part "R-EU_0204/7"))
    )
    (comp (ref "RC1_VCF")
      (value "91k")
      (footprint "eagle-import:0204_7")
      (libsource (lib "eagle-import") (part "R-EU_0204/7"))
    )
    (comp (ref "RC2_VCF")
      (value "91k")
      (footprint "eagle-import:0204_7")
      (libsource (lib "eagle-import") (part "R-EU_0204/7"))
    )
    (comp (ref "RC3")
      (value "91k")
      (footprint "eagle-import:0204_7")
      (libsource (lib "eagle-import") (part "R-EU_0204/7"))
    )
    (comp (ref "RC4")
      (value "91k")
      (footprint "eagle-import:0204_7")
      (libsource (lib "eagle-import") (part "R-EU_0204/7"))
    )
    (comp (ref "RCAL_1")
      (value "47k")
      (footprint "eagle-import:0204_7")
      (libsource (lib "eagle-import") (part "R-EU_0204/7"))
    )
    (comp (ref "RCAL_2")
      (value "100k")
      (footprint "eagle-import:0204_7")
      (libsource (lib "eagle-import") (part "R-EU_0204/7"))
    )
    (comp (ref "REE_2")
      (value "27k")
      (footprint "eagle-import:0204_7")
      (libsource (lib "eagle-import") (part "R-EU_0204/7"))
    )
    (comp (ref "REE_VCF")
      (value "1.5k")
      (footprint "eagle-import:0207_10")
      (libsource (lib "eagle-import") (part "R-EU_0207/10"))
    )
    (comp (ref "RF1_VCF")
      (value "100k")
      (footprint "eagle-import:0207_10")
      (libsource (lib "eagle-import") (part "R-EU_0207/10"))
    )
    (comp (ref "RF2_VCF")
      (value "100k")
      (footprint "eagle-import:0204_7")
      (libsource (lib "eagle-import") (part "R-EU_0204/7"))
    )
    (comp (ref "RF3")
      (value "100k")
      (footprint "eagle-import:0204_7")
      (libsource (lib "eagle-import") (part "R-EU_0204/7"))
    )
    (comp (ref "RF4")
      (value "100k")
      (footprint "eagle-import:0204_7")
      (libsource (lib "eagle-import") (part "R-EU_0204/7"))
    )
    (comp (ref "RIN1_MIXERA")
      (value "27k")
      (footprint "eagle-import:0204_7")
      (libsource (lib "eagle-import") (part "R-EU_0204/7"))
    )
    (comp (ref "RIN2_MIXERA")
      (value "27k")
      (footprint "eagle-import:0207_10")
      (libsource (lib "eagle-import") (part "R-EU_0207/10"))
    )
    (comp (ref "RIN2_MIXERB")
      (value "27k")
      (footprint "eagle-import:0204_7")
      (libsource (lib "eagle-import") (part "R-EU_0204/7"))
    )
    (comp (ref "RIN3_MIXERA")
      (value "27k")
      (footprint "eagle-import:0204_7")
      (libsource (lib "eagle-import") (part "R-EU_0204/7"))
    )
    (comp (ref "RIN3_MIXERB")
      (value "27k")
      (footprint "eagle-import:0204_7")
      (libsource (lib "eagle-import") (part "R-EU_0204/7"))
    )
    (comp (ref "RIN4_MIXERA")
      (value "27k")
      (footprint "eagle-import:0204_7")
      (libsource (lib "eagle-import") (part "R-EU_0204/7"))
    )
    (comp (ref "RIN4_MIXERB")
      (value "27k")
      (footprint "eagle-import:0204_7")
      (libsource (lib "eagle-import") (part "R-EU_0204/7"))
    )
    (comp (ref "RIN4_MIXERB1")
      (value "27k")
      (footprint "eagle-import:0204_7")
      (libsource (lib "eagle-import") (part "R-EU_0204/7"))
    )
    (comp (ref "RMODE_MIXERA")
      (value "8.2k")
      (footprint "eagle-import:0204_7")
      (libsource (lib "eagle-import") (part "R-EU_0204/7"))
    )
    (comp (ref "RMODE_MIXERB")
      (value "8.2k")
      (footprint "eagle-import:0204_7")
      (libsource (lib "eagle-import") (part "R-EU_0204/7"))
    )
    (comp (ref "ROUT_SUM_STG")
      (value "470")
      (footprint "eagle-import:0207_12")
      (libsource (lib "eagle-import") (part "R-EU_0207/12"))
    )
    (comp (ref "RRI_VCF")
      (value "51k")
      (footprint "eagle-import:0207_10")
      (libsource (lib "eagle-import") (part "R-EU_0207/10"))
    )
    (comp (ref "RSQU_2")
      (value "10k")
      (footprint "eagle-import:0204_7")
      (libsource (lib "eagle-import") (part "R-EU_0204/7"))
    )
    (comp (ref "RSTAB1_MIXERA")
      (value "470")
      (footprint "eagle-import:0204_7")
      (libsource (lib "eagle-import") (part "R-EU_0204/7"))
    )
    (comp (ref "RSTAB2_MIXERA")
      (value "470")
      (footprint "eagle-import:0207_10")
      (libsource (lib "eagle-import") (part "R-EU_0207/10"))
    )
    (comp (ref "RSTAB2_MIXERB")
      (value "470")
      (footprint "eagle-import:0207_10")
      (libsource (lib "eagle-import") (part "R-EU_0207/10"))
    )
    (comp (ref "RSTAB3_MIXERA")
      (value "470")
      (footprint "eagle-import:0204_7")
      (libsource (lib "eagle-import") (part "R-EU_0204/7"))
    )
    (comp (ref "RSTAB3_MIXERB")
      (value "470")
      (footprint "eagle-import:0204_7")
      (libsource (lib "eagle-import") (part "R-EU_0204/7"))
    )
    (comp (ref "RSTAB3_MIXERB1")
      (value "51k")
      (footprint "eagle-import:0204_7")
      (libsource (lib "eagle-import") (part "R-EU_0204/7"))
    )
    (comp (ref "RSTAB3_MIXERB2")
      (value "10k")
      (footprint "eagle-import:0204_7")
      (libsource (lib "eagle-import") (part "R-EU_0204/7"))
    )
    (comp (ref "RSTAB3_MIXERB3")
      (value "10k")
      (footprint "eagle-import:0204_7")
      (libsource (lib "eagle-import") (part "R-EU_0204/7"))
    )
    (comp (ref "RSTAB3_MIXERB4")
      (value "10k")
      (footprint "eagle-import:0204_7")
      (libsource (lib "eagle-import") (part "R-EU_0204/7"))
    )
    (comp (ref "RSTAB3_MIXERB5")
      (value "10k")
      (footprint "eagle-import:0204_7")
      (libsource (lib "eagle-import") (part "R-EU_0204/7"))
    )
    (comp (ref "RSTAB4_MIXERA")
      (value "470")
      (footprint "eagle-import:0204_7")
      (libsource (lib "eagle-import") (part "R-EU_0204/7"))
    )
    (comp (ref "RSTAB4_MIXERB")
      (value "470")
      (footprint "eagle-import:0204_7")
      (libsource (lib "eagle-import") (part "R-EU_0204/7"))
    )
    (comp (ref "RSTAB4_MIXERB1")
      (value "470")
      (footprint "eagle-import:0204_7")
      (libsource (lib "eagle-import") (part "R-EU_0204/7"))
    )
    (comp (ref "RSTAB4_MIXERB2")
      (value "470")
      (footprint "eagle-import:0204_7")
      (libsource (lib "eagle-import") (part "R-EU_0204/7"))
    )
    (comp (ref "RTEST_13700FREQ2")
      (value "27k")
      (footprint "eagle-import:0204_7")
      (libsource (lib "eagle-import") (part "R-EU_0204/7"))
    )
    (comp (ref "RTEST_LOG2")
      (value "1k")
      (footprint "eagle-import:0204_7")
      (libsource (lib "eagle-import") (part "R-EU_0204/7"))
    )
    (comp (ref "RTRI_2")
      (value "12k")
      (footprint "eagle-import:0204_7")
      (libsource (lib "eagle-import") (part "R-EU_0204/7"))
    )
    (comp (ref "R_CONV_ITOV_OUT")
      (value "33K")
      (footprint "eagle-import:0204_7")
      (libsource (lib "eagle-import") (part "R-EU_0204/7"))
    )
    (comp (ref "R_CV_FREQ1")
      (value "68k")
      (footprint "eagle-import:0204_7")
      (libsource (lib "eagle-import") (part "R-EU_0204/7"))
    )
    (comp (ref "R_CV_FREQ3")
      (value "68k")
      (footprint "eagle-import:0204_7")
      (libsource (lib "eagle-import") (part "R-EU_0204/7"))
    )
    (comp (ref "R_CV_FREQ_BIAS1")
      (value "270k")
      (footprint "eagle-import:0204_7")
      (libsource (lib "eagle-import") (part "R-EU_0204/7"))
    )
    (comp (ref "R_CV_FREQ_BIAS3")
      (value "270k")
      (footprint "eagle-import:0204_7")
      (libsource (lib "eagle-import") (part "R-EU_0204/7"))
    )
    (comp (ref "R_CV_FREQ_STAB1")
      (value "470")
      (footprint "eagle-import:0204_7")
      (libsource (lib "eagle-import") (part "R-EU_0204/7"))
    )
    (comp (ref "R_CV_FREQ_STAB3")
      (value "470")
      (footprint "eagle-import:0204_7")
      (libsource (lib "eagle-import") (part "R-EU_0204/7"))
    )
    (comp (ref "R_LIM_2")
      (value "1k")
      (footprint "eagle-import:0204_7")
      (libsource (lib "eagle-import") (part "R-EU_0204/7"))
    )
    (comp (ref "R_PD_4TH_ORDER_VCF")
      (value "100k")
      (footprint "eagle-import:0204_7")
      (libsource (lib "eagle-import") (part "R-EU_0204/7"))
    )
    (comp (ref "R_PD_411_IN_PULSE1")
      (value "100k")
      (footprint "eagle-import:0207_10")
      (libsource (lib "eagle-import") (part "R-EU_0207/10"))
    )
    (comp (ref "R_PD_411_IN_SAW1")
      (value "100k")
      (footprint "eagle-import:0204_7")
      (libsource (lib "eagle-import") (part "R-EU_0204/7"))
    )
    (comp (ref "R_PD_411_IN_SYNC1")
      (value "100k")
      (footprint "eagle-import:0204_7")
      (libsource (lib "eagle-import") (part "R-EU_0204/7"))
    )
    (comp (ref "R_PD_411_IN_TRI1")
      (value "100k")
      (footprint "eagle-import:0204_7")
      (libsource (lib "eagle-import") (part "R-EU_0204/7"))
    )
    (comp (ref "R_RES_VCF")
      (value "100k")
      (footprint "eagle-import:0204_7")
      (libsource (lib "eagle-import") (part "R-EU_0204/7"))
    )
    (comp (ref "R_RST")
      (value "10k")
      (footprint "eagle-import:0207_10")
      (libsource (lib "eagle-import") (part "R-US_0207/10"))
    )
    (comp (ref "R_SW1A")
      (value "10k")
      (footprint "eagle-import:0207_10")
      (libsource (lib "eagle-import") (part "R-US_0207/10"))
    )
    (comp (ref "R_SW1B")
      (value "10k")
      (footprint "eagle-import:0207_10")
      (libsource (lib "eagle-import") (part "R-US_0207/10"))
    )
    (comp (ref "R_SW2A")
      (value "10k")
      (footprint "eagle-import:0207_10")
      (libsource (lib "eagle-import") (part "R-US_0207/10"))
    )
    (comp (ref "R_SW2B")
      (value "10k")
      (footprint "eagle-import:0207_10")
      (libsource (lib "eagle-import") (part "R-US_0207/10"))
    )
    (comp (ref "R_SYNC1")
      (value "470k")
      (footprint "eagle-import:0204_7")
      (libsource (lib "eagle-import") (part "R-EU_0204/7"))
    )
    (comp (ref "R_SYNC3")
      (value "470k")
      (footprint "eagle-import:0204_7")
      (libsource (lib "eagle-import") (part "R-EU_0204/7"))
    )
    (comp (ref "S1")
      (value "10-XX")
      (footprint "eagle-import:B3F-10XX")
      (fields (field (name "MPN") "B3F-1000"))
      (libsource (lib "eagle-import") (part "10-XX"))
    )
    (comp (ref "S2")
      (value "10-XX")
      (footprint "eagle-import:B3F-10XX")
      (fields (field (name "MPN") "B3F-1000"))
      (libsource (lib "eagle-import") (part "10-XX"))
    )
    (comp (ref "STM32L432KC_CONN_")
      (value "NUCLEO-F303K8")
      (footprint "eagle-import:MODULE_NUCLEO-F303K8")
      (fields (field (name "DIGI-KEY_PART_NUMBER") "497-15981-ND") (field (name "MF") "STMicroelectronics"))
      (libsource (lib "eagle-import") (part "NUCLEO-F303K8"))
    )
    (comp (ref "SUBBASS2")
      (value "HEF4027BP")
      (footprint "eagle-import:DIP254P762X420-16")
      (fields (field (name "MF") "NXP Semiconductors"))
      (libsource (lib "eagle-import") (part "HEF4027BP"))
    )
    (comp (ref "SUM_STG_C")
      (value "560p")
      (footprint "eagle-import:C075-032X103")
      (libsource (lib "eagle-import") (part "rcl_334_C-EU075-032X103"))
    )
    (comp (ref "SUM_STG_HEADER")
      (value "MA04-2")
      (footprint "eagle-import:MA04-2")
      (libsource (lib "eagle-import") (part "MA04-2"))
    )
    (comp (ref "SUM_STG_R")
      (value "27k")
      (footprint "eagle-import:0207_10")
      (libsource (lib "eagle-import") (part "R-EU_0207/10"))
    )
    (comp (ref "TP_13700_SQU2")
      (value "TESTPOINT")
      (footprint "eagle-import:TESTPOINT_63")
      (libsource (lib "eagle-import") (part "TESTPOINT"))
    )
    (comp (ref "TP_13700_TRI2")
      (value "TESTPOINT")
      (footprint "eagle-import:TESTPOINT_63")
      (libsource (lib "eagle-import") (part "TESTPOINT"))
    )
    (comp (ref "TP_CV_2")
      (value "TESTPOINT")
      (footprint "eagle-import:TESTPOINT_63")
      (libsource (lib "eagle-import") (part "TESTPOINT"))
    )
    (comp (ref "TP_PULSE1")
      (value "TESTPOINT")
      (footprint "eagle-import:TESTPOINT_63")
      (libsource (lib "eagle-import") (part "TESTPOINT"))
    )
    (comp (ref "TP_PULSE3")
      (value "TESTPOINT")
      (footprint "eagle-import:TESTPOINT_63")
      (libsource (lib "eagle-import") (part "TESTPOINT"))
    )
    (comp (ref "TP_SAW1")
      (value "TESTPOINT")
      (footprint "eagle-import:TESTPOINT_63")
      (libsource (lib "eagle-import") (part "TESTPOINT"))
    )
    (comp (ref "TP_SAW3")
      (value "TESTPOINT")
      (footprint "eagle-import:TESTPOINT_63")
      (libsource (lib "eagle-import") (part "TESTPOINT"))
    )
    (comp (ref "TP_TRI1")
      (value "TESTPOINT")
      (footprint "eagle-import:TESTPOINT_63")
      (libsource (lib "eagle-import") (part "TESTPOINT"))
    )
    (comp (ref "TP_TRI3")
      (value "TESTPOINT")
      (footprint "eagle-import:TESTPOINT_63")
      (libsource (lib "eagle-import") (part "TESTPOINT"))
    )
    (comp (ref "U1")
      (value "ANALOG_DEVICES_AD5391BSTZ-3ANALOG_DEVICES_AD5391BSTZ-3_0_0")
      (footprint "eagle-import:ANALOG_DEVICES_AD5391BSTZ-3_0")
      (fields (field (name "MF") "Analog Devices") (field (name "MPN") "AD5391BSTZ-3"))
      (libsource (lib "eagle-import") (part "ANALOG_DEVICES_AD5391BSTZ-3ANALOG_DEVICES_AD5391BSTZ-3_0_0"))
    )
    (comp (ref "VCF")
      (value "AS3320")
      (footprint "eagle-import:DIL18")
      (libsource (lib "eagle-import") (part "AS3320"))
    )
    (comp (ref "VCF_ANALOG_SW")
      (value "DG413DJN")
      (footprint "eagle-import:DIL16")
      (libsource (lib "eagle-import") (part "DG413DJN"))
    )
    (comp (ref "VCF_JUMPER")
      (value "MA04-1")
      (footprint "eagle-import:MA04-1")
      (libsource (lib "eagle-import") (part "MA04-1"))
    )
    (comp (ref "VCO1")
      (value "LM13700N")
      (footprint "eagle-import:DIL16")
      (libsource (lib "eagle-import") (part "LM13700N"))
    )
    (comp (ref "VCO2")
      (value "LM13700N")
      (footprint "eagle-import:DIL16")
      (libsource (lib "eagle-import") (part "LM13700N"))
    )
  )
  (nets
    (net (code "1") (name "+15V") (class "Default")
      (node (ref "3") (pin "13") (pinfunction "VDD_13") (pintype "power_in"))
      (node (ref "3340A") (pin "16") (pinfunction "VCC_16") (pintype "bidirectional"))
      (node (ref "3340B") (pin "16") (pinfunction "VCC_16") (pintype "bidirectional"))
      (node (ref "C+15VPOL_VCF") (pin "2") (pinfunction "2_2") (pintype "passive"))
      (node (ref "C+15V_SUM_STG") (pin "2") (pinfunction "2_2") (pintype "passive"))
      (node (ref "C+15V_VCF") (pin "2") (pinfunction "2_2") (pintype "passive"))
      (node (ref "CDEC+15V6") (pin "1") (pinfunction "1_1") (pintype "passive"))
      (node (ref "CDEC+15V7") (pin "1") (pinfunction "1_1") (pintype "passive"))
      (node (ref "CDEC+15VPOL_MIXERB") (pin "2") (pinfunction "2_2") (pintype "passive"))
      (node (ref "CDEC+15V_MIXERB") (pin "2") (pinfunction "2_2") (pintype "passive"))
      (node (ref "CDEC_3340A2") (pin "2") (pinfunction "2_2") (pintype "passive"))
      (node (ref "CDEC_3340A3") (pin "2") (pinfunction "2_2") (pintype "passive"))
      (node (ref "CDEC_3340A6") (pin "2") (pinfunction "2_2") (pintype "passive"))
      (node (ref "CDEC_3340A7") (pin "2") (pinfunction "2_2") (pintype "passive"))
      (node (ref "CONV_ITOV_OUT") (pin "7") (pinfunction "V+_7") (pintype "power_in"))
      (node (ref "EXPCONV2") (pin "7") (pinfunction "V+_7") (pintype "power_in"))
      (node (ref "MIXER_A") (pin "16") (pinfunction "V+_16") (pintype "bidirectional"))
      (node (ref "MIXER_B") (pin "16") (pinfunction "V+_16") (pintype "bidirectional"))
      (node (ref "OPAMP_SUM_STG") (pin "7") (pinfunction "V+_7") (pintype "power_in"))
      (node (ref "R2_PWM1") (pin "2") (pinfunction "2_2") (pintype "passive"))
      (node (ref "R2_PWM3") (pin "2") (pinfunction "2_2") (pintype "passive"))
      (node (ref "R8_1") (pin "2") (pinfunction "2_2") (pintype "passive"))
      (node (ref "R8_3") (pin "2") (pinfunction "2_2") (pintype "passive"))
      (node (ref "RMODE_MIXERA") (pin "1") (pinfunction "1_1") (pintype "passive"))
      (node (ref "RMODE_MIXERB") (pin "1") (pinfunction "1_1") (pintype "passive"))
      (node (ref "RSTAB3_MIXERB2") (pin "1") (pinfunction "1_1") (pintype "passive"))
      (node (ref "RSTAB3_MIXERB4") (pin "1") (pinfunction "1_1") (pintype "passive"))
      (node (ref "R_CV_FREQ_BIAS1") (pin "2") (pinfunction "2_2") (pintype "passive"))
      (node (ref "R_CV_FREQ_BIAS3") (pin "2") (pinfunction "2_2") (pintype "passive"))
      (node (ref "VCF") (pin "14") (pinfunction "V+_14") (pintype "bidirectional"))
      (node (ref "VCF_ANALOG_SW") (pin "13") (pinfunction "V+_13") (pintype "power_in"))
      (node (ref "VCO1") (pin "11") (pinfunction "V+_11") (pintype "power_in"))
      (node (ref "VCO2") (pin "11") (pinfunction "V+_11") (pintype "power_in"))
    )
    (net (code "2") (name "-15V") (class "Default")
      (node (ref "3") (pin "4") (pinfunction "VSS_4") (pintype "power_in"))
      (node (ref "C-15V_SUM_STG") (pin "1") (pinfunction "1_1") (pintype "passive"))
      (node (ref "CDEC-15V6") (pin "2") (pinfunction "2_2") (pintype "passive"))
      (node (ref "CDEC-15V7") (pin "2") (pinfunction "2_2") (pintype "passive"))
      (node (ref "CDEC-15VPOL_MIXERB") (pin "1") (pinfunction "1_1") (pintype "passive"))
      (node (ref "CDEC-15V_MIXERB") (pin "1") (pinfunction "1_1") (pintype "passive"))
      (node (ref "CONV_ITOV_OUT") (pin "4") (pinfunction "V-_4") (pintype "power_in"))
      (node (ref "EXPCONV2") (pin "4") (pinfunction "V-_4") (pintype "power_in"))
      (node (ref "MIXER_A") (pin "9") (pinfunction "V-_9") (pintype "bidirectional"))
      (node (ref "MIXER_B") (pin "9") (pinfunction "V-_9") (pintype "bidirectional"))
      (node (ref "OPAMP_SUM_STG") (pin "4") (pinfunction "V-_4") (pintype "power_in"))
      (node (ref "R3_1") (pin "1") (pinfunction "1_1") (pintype "passive"))
      (node (ref "R3_3") (pin "1") (pinfunction "1_1") (pintype "passive"))
      (node (ref "RB1_VCF") (pin "1") (pinfunction "1_1") (pintype "passive"))
      (node (ref "RB2") (pin "1") (pinfunction "1_1") (pintype "passive"))
      (node (ref "RB3_VCF") (pin "1") (pinfunction "1_1") (pintype "passive"))
      (node (ref "RBIAS_EXPCONV2") (pin "1") (pinfunction "1_1") (pintype "passive"))
      (node (ref "REE_VCF") (pin "1") (pinfunction "1_1") (pintype "passive"))
      (node (ref "RSQU_2") (pin "1") (pinfunction "1_1") (pintype "passive"))
      (node (ref "RTRI_2") (pin "1") (pinfunction "1_1") (pintype "passive"))
      (node (ref "VCF_ANALOG_SW") (pin "4") (pinfunction "V-_4") (pintype "power_in"))
      (node (ref "VCO2") (pin "6") (pinfunction "V-_6") (pintype "power_in"))
    )
    (net (code "3") (name "5V") (class "Default")
      (node (ref "3") (pin "12") (pinfunction "VL_12") (pintype "power_in"))
      (node (ref "C5VPOL_VCF") (pin "1") (pinfunction "1_1") (pintype "passive"))
      (node (ref "C5V_VCF") (pin "1") (pinfunction "1_1") (pintype "passive"))
      (node (ref "CDEC_411B6") (pin "1") (pinfunction "1_1") (pintype "passive"))
      (node (ref "CDEC_411B7") (pin "1") (pinfunction "1_1") (pintype "passive"))
      (node (ref "CDEC_5V1") (pin "1") (pinfunction "1_1") (pintype "passive"))
      (node (ref "CDEC_5V4") (pin "1") (pinfunction "1_1") (pintype "passive"))
      (node (ref "CDEC_AVDD1") (pin "2") (pinfunction "2_2") (pintype "passive"))
      (node (ref "CDEC_AVDD1_100N") (pin "2") (pinfunction "2_2") (pintype "passive"))
      (node (ref "CDEC_AVDD2") (pin "2") (pinfunction "2_2") (pintype "passive"))
      (node (ref "CDEC_AVDD2_100N") (pin "2") (pinfunction "2_2") (pintype "passive"))
      (node (ref "CDEC_DVDD1") (pin "2") (pinfunction "2_2") (pintype "passive"))
      (node (ref "CDEC_DVDD2") (pin "2") (pinfunction "2_2") (pintype "passive"))
      (node (ref "CDEC_MCP") (pin "1") (pinfunction "1_1") (pintype "passive"))
      (node (ref "IC1") (pin "9") (pinfunction "VDD_9") (pintype "power_in"))
      (node (ref "IC_EEPROM") (pin "2") (pinfunction "A1_2") (pintype "input"))
      (node (ref "IC_EEPROM") (pin "3") (pinfunction "A2_3") (pintype "input"))
      (node (ref "IC_EEPROM") (pin "8") (pinfunction "VCC_8") (pintype "power_in"))
      (node (ref "R1_8") (pin "1") (pinfunction "1_1") (pintype "passive"))
      (node (ref "R3_EXPCONV2") (pin "2") (pinfunction "2_2") (pintype "passive"))
      (node (ref "R_PD_411_IN_SAW1") (pin "2") (pinfunction "2_2") (pintype "passive"))
      (node (ref "R_RST") (pin "1") (pinfunction "1_1") (pintype "passive"))
      (node (ref "R_SW1A") (pin "1") (pinfunction "1_1") (pintype "passive"))
      (node (ref "R_SW2A") (pin "1") (pinfunction "1_1") (pintype "passive"))
      (node (ref "STM32L432KC_CONN_") (pin "4.1") (pinfunction "VIN_4.1") (pintype "bidirectional"))
      (node (ref "SUBBASS2") (pin "11") (pinfunction "1K_11") (pintype "input"))
      (node (ref "SUBBASS2") (pin "16") (pinfunction "VDD_16") (pintype "power_in"))
      (node (ref "U1") (pin "1") (pinfunction "~{CLR}_1") (pintype "input"))
      (node (ref "U1") (pin "32") (pinfunction "AVDD_2_32") (pintype "power_in"))
      (node (ref "U1") (pin "42") (pinfunction "~{I2C}_42") (pintype "input"))
      (node (ref "U1") (pin "44") (pinfunction "1_DVDD_44") (pintype "power_in"))
      (node (ref "U1") (pin "45") (pinfunction "2_DVDD_45") (pintype "power_in"))
      (node (ref "U1") (pin "47") (pinfunction "3_DVDD_47") (pintype "power_in"))
      (node (ref "U1") (pin "8") (pinfunction "AVDD_1_8") (pintype "power_in"))
      (node (ref "VCF_ANALOG_SW") (pin "12") (pinfunction "VL_12") (pintype "input"))
    )
    (net (code "4") (name "411_IN_PULSE") (class "Default")
      (node (ref "3") (pin "8") (pinfunction "IN_8") (pintype "input"))
      (node (ref "IC1") (pin "22") (pinfunction "GPA1_22") (pintype "bidirectional"))
      (node (ref "R_PD_411_IN_PULSE1") (pin "2") (pinfunction "2_2") (pintype "passive"))
    )
    (net (code "5") (name "411_IN_SAW") (class "Default")
      (node (ref "3") (pin "9") (pinfunction "IN_9") (pintype "input"))
      (node (ref "IC1") (pin "23") (pinfunction "GPA2_23") (pintype "bidirectional"))
      (node (ref "R_PD_411_IN_SAW1") (pin "1") (pinfunction "1_1") (pintype "passive"))
    )
    (net (code "6") (name "411_IN_SYNC") (class "Default")
      (node (ref "3") (pin "16") (pinfunction "IN_16") (pintype "input"))
      (node (ref "IC1") (pin "24") (pinfunction "GPA3_24") (pintype "bidirectional"))
      (node (ref "R_PD_411_IN_SYNC1") (pin "1") (pinfunction "1_1") (pintype "passive"))
    )
    (net (code "7") (name "411_IN_TRI") (class "Default")
      (node (ref "3") (pin "1") (pinfunction "IN_1") (pintype "input"))
      (node (ref "IC1") (pin "21") (pinfunction "GPA0_21") (pintype "bidirectional"))
      (node (ref "R_PD_411_IN_TRI1") (pin "1") (pinfunction "1_1") (pintype "passive"))
    )
    (net (code "8") (name "2164_IN1_MIXA") (class "Default")
      (node (ref "MIXER_A") (pin "2") (pinfunction "I_IN_2") (pintype "bidirectional"))
      (node (ref "RIN1_MIXERA") (pin "1") (pinfunction "1_1") (pintype "passive"))
      (node (ref "RSTAB1_MIXERA") (pin "1") (pinfunction "1_1") (pintype "passive"))
    )
    (net (code "9") (name "2164_IN2_MIXA") (class "Default")
      (node (ref "MIXER_A") (pin "7") (pinfunction "I_IN_7") (pintype "bidirectional"))
      (node (ref "RIN2_MIXERA") (pin "1") (pinfunction "1_1") (pintype "passive"))
      (node (ref "RSTAB2_MIXERA") (pin "1") (pinfunction "1_1") (pintype "passive"))
    )
    (net (code "10") (name "2164_IN2_MIXB") (class "Default")
      (node (ref "MIXER_B") (pin "7") (pinfunction "I_IN_7") (pintype "bidirectional"))
      (node (ref "RIN2_MIXERB") (pin "1") (pinfunction "1_1") (pintype "passive"))
      (node (ref "RSTAB2_MIXERB") (pin "1") (pinfunction "1_1") (pintype "passive"))
    )
    (net (code "11") (name "2164_IN3_MIXA") (class "Default")
      (node (ref "MIXER_A") (pin "10") (pinfunction "I_IN_10") (pintype "bidirectional"))
      (node (ref "RIN3_MIXERA") (pin "1") (pinfunction "1_1") (pintype "passive"))
      (node (ref "RSTAB3_MIXERA") (pin "1") (pinfunction "1_1") (pintype "passive"))
    )
    (net (code "12") (name "2164_IN3_MIXB") (class "Default")
      (node (ref "MIXER_B") (pin "10") (pinfunction "I_IN_10") (pintype "bidirectional"))
      (node (ref "RIN3_MIXERB") (pin "1") (pinfunction "1_1") (pintype "passive"))
      (node (ref "RSTAB3_MIXERB") (pin "1") (pinfunction "1_1") (pintype "passive"))
    )
    (net (code "13") (name "2164_IN4_MIXA") (class "Default")
      (node (ref "MIXER_A") (pin "15") (pinfunction "I_IN_15") (pintype "bidirectional"))
      (node (ref "RIN4_MIXERA") (pin "1") (pinfunction "1_1") (pintype "passive"))
      (node (ref "RSTAB4_MIXERA") (pin "1") (pinfunction "1_1") (pintype "passive"))
    )
    (net (code "14") (name "2164_IN4_MIXB") (class "Default")
      (node (ref "MIXER_B") (pin "15") (pinfunction "I_IN_15") (pintype "bidirectional"))
      (node (ref "RIN4_MIXERB") (pin "1") (pinfunction "1_1") (pintype "passive"))
      (node (ref "RSTAB4_MIXERB") (pin "1") (pinfunction "1_1") (pintype "passive"))
    )
    (net (code "15") (name "2164_MODE_MIXA") (class "Default")
      (node (ref "MIXER_A") (pin "1") (pinfunction "MODE_1") (pintype "bidirectional"))
      (node (ref "RMODE_MIXERA") (pin "2") (pinfunction "2_2") (pintype "passive"))
    )
    (net (code "16") (name "2164_MODE_MIXB") (class "Default")
      (node (ref "MIXER_B") (pin "1") (pinfunction "MODE_1") (pintype "bidirectional"))
      (node (ref "RMODE_MIXERB") (pin "2") (pinfunction "2_2") (pintype "passive"))
    )
    (net (code "17") (name "2164_OUT2_MIXA") (class "Default")
      (node (ref "JP_MIXER_A") (pin "2") (pinfunction "2_2") (pintype "passive"))
      (node (ref "MIXER_A") (pin "5") (pinfunction "I_OUT_5") (pintype "bidirectional"))
    )
    (net (code "18") (name "2164_OUT2_MIXB") (class "Default")
      (node (ref "JP_MIXER_B") (pin "4") (pinfunction "4_4") (pintype "passive"))
      (node (ref "MIXER_B") (pin "5") (pinfunction "I_OUT_5") (pintype "bidirectional"))
    )
    (net (code "19") (name "2164_OUT3_MIXA") (class "Default")
      (node (ref "JP_MIXER_A") (pin "6") (pinfunction "6_6") (pintype "passive"))
      (node (ref "MIXER_A") (pin "12") (pinfunction "I_OUT_12") (pintype "bidirectional"))
    )
    (net (code "20") (name "2164_OUT4_MIXA") (class "Default")
      (node (ref "JP_MIXER_A") (pin "8") (pinfunction "8_8") (pintype "passive"))
      (node (ref "MIXER_A") (pin "13") (pinfunction "I_OUT_13") (pintype "bidirectional"))
    )
    (net (code "21") (name "2164_OUT4_MIXB") (class "Default")
      (node (ref "JP_MIXER_B") (pin "6") (pinfunction "6_6") (pintype "passive"))
      (node (ref "MIXER_B") (pin "13") (pinfunction "I_OUT_13") (pintype "bidirectional"))
    )
    (net (code "22") (name "AGND") (class "Default")
      (node (ref "3") (pin "5") (pinfunction "GND_5") (pintype "power_in"))
      (node (ref "3340A") (pin "12") (pinfunction "GND_12") (pintype "bidirectional"))
      (node (ref "3340B") (pin "12") (pinfunction "GND_12") (pintype "bidirectional"))
      (node (ref "C+15VPOL_VCF") (pin "1") (pinfunction "1_1") (pintype "passive"))
      (node (ref "C+15V_SUM_STG") (pin "1") (pinfunction "1_1") (pintype "passive"))
      (node (ref "C+15V_VCF") (pin "1") (pinfunction "1_1") (pintype "passive"))
      (node (ref "C-15VPOL_VCF") (pin "2") (pinfunction "2_2") (pintype "passive"))
      (node (ref "C-15V_SUM_STG") (pin "2") (pinfunction "2_2") (pintype "passive"))
      (node (ref "C-15V_VCF") (pin "2") (pinfunction "2_2") (pintype "passive"))
      (node (ref "C10") (pin "1") (pinfunction "1_1") (pintype "passive"))
      (node (ref "C2_SYNC1") (pin "1") (pinfunction "1_1") (pintype "passive"))
      (node (ref "C2_SYNC3") (pin "1") (pinfunction "1_1") (pintype "passive"))
      (node (ref "C3") (pin "1") (pinfunction "1_1") (pintype "passive"))
      (node (ref "C4") (pin "1") (pinfunction "1_1") (pintype "passive"))
      (node (ref "C4_1") (pin "2") (pinfunction "2_2") (pintype "passive"))
      (node (ref "C4_3") (pin "2") (pinfunction "2_2") (pintype "passive"))
      (node (ref "C5") (pin "1") (pinfunction "1_1") (pintype "passive"))
      (node (ref "C5VPOL_VCF") (pin "2") (pinfunction "2_2") (pintype "passive"))
      (node (ref "C5V_VCF") (pin "2") (pinfunction "2_2") (pintype "passive"))
      (node (ref "CDEC+15V6") (pin "2") (pinfunction "2_2") (pintype "passive"))
      (node (ref "CDEC+15V7") (pin "2") (pinfunction "2_2") (pintype "passive"))
      (node (ref "CDEC+15VPOL_MIXERB") (pin "1") (pinfunction "1_1") (pintype "passive"))
      (node (ref "CDEC+15V_MIXERB") (pin "1") (pinfunction "1_1") (pintype "passive"))
      (node (ref "CDEC-15V6") (pin "1") (pinfunction "1_1") (pintype "passive"))
      (node (ref "CDEC-15V7") (pin "1") (pinfunction "1_1") (pintype "passive"))
      (node (ref "CDEC-15VPOL_MIXERB") (pin "2") (pinfunction "2_2") (pintype "passive"))
      (node (ref "CDEC-15V_MIXERB") (pin "2") (pinfunction "2_2") (pintype "passive"))
      (node (ref "CDEC_3340A2") (pin "1") (pinfunction "1_1") (pintype "passive"))
      (node (ref "CDEC_3340A3") (pin "1") (pinfunction "1_1") (pintype "passive"))
      (node (ref "CDEC_3340A6") (pin "1") (pinfunction "1_1") (pintype "passive"))
      (node (ref "CDEC_3340A7") (pin "1") (pinfunction "1_1") (pintype "passive"))
      (node (ref "CDEC_3340B2") (pin "1") (pinfunction "1_1") (pintype "passive"))
      (node (ref "CDEC_3340B3") (pin "1") (pinfunction "1_1") (pintype "passive"))
      (node (ref "CDEC_3340B6") (pin "1") (pinfunction "1_1") (pintype "passive"))
      (node (ref "CDEC_3340B7") (pin "1") (pinfunction "1_1") (pintype "passive"))
      (node (ref "CDEC_411B6") (pin "2") (pinfunction "2_2") (pintype "passive"))
      (node (ref "CDEC_411B7") (pin "2") (pinfunction "2_2") (pintype "passive"))
      (node (ref "CDEC_5V1") (pin "2") (pinfunction "2_2") (pintype "passive"))
      (node (ref "CDEC_5V4") (pin "2") (pinfunction "2_2") (pintype "passive"))
      (node (ref "CDEC_AVDD1") (pin "1") (pinfunction "1_1") (pintype "passive"))
      (node (ref "CDEC_AVDD1_100N") (pin "1") (pinfunction "1_1") (pintype "passive"))
      (node (ref "CDEC_AVDD2") (pin "1") (pinfunction "1_1") (pintype "passive"))
      (node (ref "CDEC_AVDD2_100N") (pin "1") (pinfunction "1_1") (pintype "passive"))
      (node (ref "CDEC_DVDD1") (pin "1") (pinfunction "1_1") (pintype "passive"))
      (node (ref "CDEC_DVDD2") (pin "1") (pinfunction "1_1") (pintype "passive"))
      (node (ref "CDEC_MCP") (pin "2") (pinfunction "2_2") (pintype "passive"))
      (node (ref "CDEC_VREF") (pin "2") (pinfunction "2_2") (pintype "passive"))
      (node (ref "CF_2") (pin "1") (pinfunction "1_1") (pintype "passive"))
      (node (ref "CONN_UART_RPI") (pin "1") (pinfunction "1_1") (pintype "passive"))
      (node (ref "CONV_ITOV_OUT") (pin "3") (pinfunction "+IN_3") (pintype "input"))
      (node (ref "CSTAB1_MIXERA") (pin "1") (pinfunction "1_1") (pintype "passive"))
      (node (ref "CSTAB2_MIXERA") (pin "1") (pinfunction "1_1") (pintype "passive"))
      (node (ref "CSTAB2_MIXERB") (pin "1") (pinfunction "1_1") (pintype "passive"))
      (node (ref "CSTAB3") (pin "1") (pinfunction "1_1") (pintype "passive"))
      (node (ref "CSTAB3_MIXERA") (pin "1") (pinfunction "1_1") (pintype "passive"))
      (node (ref "CSTAB3_MIXERB") (pin "1") (pinfunction "1_1") (pintype "passive"))
      (node (ref "CSTAB4_MIXERA") (pin "1") (pinfunction "1_1") (pintype "passive"))
      (node (ref "CSTAB8") (pin "1") (pinfunction "1_1") (pintype "passive"))
      (node (ref "C_1") (pin "1") (pinfunction "1_1") (pintype "passive"))
      (node (ref "C_3") (pin "1") (pinfunction "1_1") (pintype "passive"))
      (node (ref "C_CV_FREQ_STAB1") (pin "1") (pinfunction "1_1") (pintype "passive"))
      (node (ref "C_CV_FREQ_STAB3") (pin "1") (pinfunction "1_1") (pintype "passive"))
      (node (ref "C_SW1") (pin "2") (pinfunction "2_2") (pintype "passive"))
      (node (ref "C_SW2") (pin "2") (pinfunction "2_2") (pintype "passive"))
      (node (ref "EXPCONV2") (pin "3") (pinfunction "+IN_3") (pintype "input"))
      (node (ref "IC1") (pin "10") (pinfunction "VSS_10") (pintype "power_in"))
      (node (ref "IC1") (pin "15") (pinfunction "A0_15") (pintype "input"))
      (node (ref "IC1") (pin "16") (pinfunction "A1_16") (pintype "input"))
      (node (ref "IC1") (pin "17") (pinfunction "A2_17") (pintype "input"))
      (node (ref "IC_EEPROM") (pin "1") (pinfunction "A0_1") (pintype "input"))
      (node (ref "IC_EEPROM") (pin "4") (pinfunction "GND_4") (pintype "power_in"))
      (node (ref "IC_EEPROM") (pin "7") (pinfunction "WP_7") (pintype "input"))
      (node (ref "JACK_SUM_STG") (pin "1") (pinfunction "1_1") (pintype "passive"))
      (node (ref "MIXER_A") (pin "8") (pinfunction "GND_8") (pintype "bidirectional"))
      (node (ref "MIXER_B") (pin "8") (pinfunction "GND_8") (pintype "bidirectional"))
      (node (ref "OPAMP_SUM_STG") (pin "3") (pinfunction "+IN_3") (pintype "input"))
      (node (ref "POT_SUM_STG") (pin "1") (pinfunction "A_1") (pintype "passive"))
      (node (ref "R11_1") (pin "2") (pinfunction "2_2") (pintype "passive"))
      (node (ref "R11_3") (pin "2") (pinfunction "2_2") (pintype "passive"))
      (node (ref "R1_7") (pin "1") (pinfunction "1_1") (pintype "passive"))
      (node (ref "R1_PWM1") (pin "2") (pinfunction "2_2") (pintype "passive"))
      (node (ref "R1_PWM3") (pin "2") (pinfunction "2_2") (pintype "passive"))
      (node (ref "R1_VCF") (pin "2") (pinfunction "2_2") (pintype "passive"))
      (node (ref "R2_7") (pin "1") (pinfunction "1_1") (pintype "passive"))
      (node (ref "R2_8") (pin "2") (pinfunction "2_2") (pintype "passive"))
      (node (ref "R2_EXPCONV2") (pin "2") (pinfunction "2_2") (pintype "passive"))
      (node (ref "R3_4") (pin "1") (pinfunction "1_1") (pintype "passive"))
      (node (ref "R4_EXPCONV2") (pin "2") (pinfunction "2_2") (pintype "passive"))
      (node (ref "R5_1") (pin "2") (pinfunction "2_2") (pintype "passive"))
      (node (ref "R5_3") (pin "2") (pinfunction "2_2") (pintype "passive"))
      (node (ref "RA_2") (pin "1") (pinfunction "1_1") (pintype "passive"))
      (node (ref "RCAL_2") (pin "2") (pinfunction "2_2") (pintype "passive"))
      (node (ref "REE_2") (pin "2") (pinfunction "2_2") (pintype "passive"))
      (node (ref "RSTAB3_MIXERB3") (pin "2") (pinfunction "2_2") (pintype "passive"))
      (node (ref "RSTAB3_MIXERB5") (pin "1") (pinfunction "1_1") (pintype "passive"))
      (node (ref "RSTAB4_MIXERB1") (pin "1") (pinfunction "1_1") (pintype "passive"))
      (node (ref "RTEST_LOG2") (pin "2") (pinfunction "2_2") (pintype "passive"))
      (node (ref "R_PD_411_IN_PULSE1") (pin "1") (pinfunction "1_1") (pintype "passive"))
      (node (ref "R_PD_411_IN_SYNC1") (pin "2") (pinfunction "2_2") (pintype "passive"))
      (node (ref "R_PD_411_IN_TRI1") (pin "2") (pinfunction "2_2") (pintype "passive"))
      (node (ref "R_PD_4TH_ORDER_VCF") (pin "1") (pinfunction "1_1") (pintype "passive"))
      (node (ref "R_SYNC1") (pin "1") (pinfunction "1_1") (pintype "passive"))
      (node (ref "R_SYNC3") (pin "1") (pinfunction "1_1") (pintype "passive"))
      (node (ref "S1") (pin "1") (pinfunction "S_1") (pintype "passive"))
      (node (ref "S1") (pin "2") (pinfunction "S1_2") (pintype "passive"))
      (node (ref "S2") (pin "1") (pinfunction "S_1") (pintype "passive"))
      (node (ref "S2") (pin "2") (pinfunction "S1_2") (pintype "passive"))
      (node (ref "STM32L432KC_CONN_") (pin "3.4") (pinfunction "GND_3.4") (pintype "bidirectional"))
      (node (ref "STM32L432KC_CONN_") (pin "4.2") (pinfunction "GND_4.2") (pintype "bidirectional"))
      (node (ref "SUBBASS2") (pin "12") (pinfunction "1CD_12") (pintype "input"))
      (node (ref "SUBBASS2") (pin "8") (pinfunction "VSS_8") (pintype "passive"))
      (node (ref "SUBBASS2") (pin "9") (pinfunction "1SD_9") (pintype "input"))
      (node (ref "U1") (pin "14") (pinfunction "AGND_1_14") (pintype "power_in"))
      (node (ref "U1") (pin "26") (pinfunction "DAC_GND_2_26") (pintype "power_in"))
      (node (ref "U1") (pin "27") (pinfunction "SIGNAL_GND_2_27") (pintype "power_in"))
      (node (ref "U1") (pin "31") (pinfunction "AGND_2_31") (pintype "power_in"))
      (node (ref "U1") (pin "4") (pinfunction "REF_GND_4") (pintype "power_in"))
      (node (ref "U1") (pin "40") (pinfunction "DCEN/AD1_40") (pintype "input"))
      (node (ref "U1") (pin "41") (pinfunction "PD_41") (pintype "input"))
      (node (ref "U1") (pin "43") (pinfunction "1_DGND_43") (pintype "power_in"))
      (node (ref "U1") (pin "46") (pinfunction "2_DGND_46") (pintype "power_in"))
      (node (ref "U1") (pin "52") (pinfunction "3_DGND_52") (pintype "power_in"))
      (node (ref "U1") (pin "6") (pinfunction "SIGNAL_GND_1_6") (pintype "power_in"))
      (node (ref "U1") (pin "7") (pinfunction "DAC_GND_1_7") (pintype "power_in"))
      (node (ref "VCF") (pin "3") (pinfunction "GND_3") (pintype "bidirectional"))
      (node (ref "VCF_ANALOG_SW") (pin "5") (pinfunction "GND_5") (pintype "power_in"))
      (node (ref "VCO1") (pin "6") (pinfunction "V-_6") (pintype "power_in"))
      (node (ref "VCO2") (pin "4") (pinfunction "IN_N_4") (pintype "input"))
    )
    (net (code "23") (name "BIAS_4027_VCO13700") (class "Default")
      (node (ref "CIN_2") (pin "1") (pinfunction "1_1") (pintype "passive"))
      (node (ref "D_2") (pin "A") (pinfunction "A_A") (pintype "passive"))
      (node (ref "R1_8") (pin "2") (pinfunction "2_2") (pintype "passive"))
      (node (ref "R2_8") (pin "1") (pinfunction "1_1") (pintype "passive"))
    )
    (net (code "24") (name "CALIB_3340A") (class "Default")
      (node (ref "R5_3") (pin "1") (pinfunction "1_1") (pintype "passive"))
      (node (ref "R6_3") (pin "1") (pinfunction "1_1") (pintype "passive"))
      (node (ref "STM32L432KC_CONN_") (pin "3.12") (pinfunction "PA8_3.12") (pintype "bidirectional"))
    )
    (net (code "25") (name "CALIB_3340B") (class "Default")
      (node (ref "R5_1") (pin "1") (pinfunction "1_1") (pintype "passive"))
      (node (ref "R6_1") (pin "1") (pinfunction "1_1") (pintype "passive"))
      (node (ref "STM32L432KC_CONN_") (pin "3.1") (pinfunction "PA9_3.1") (pintype "bidirectional"))
    )
    (net (code "26") (name "CALIB_13700") (class "Default")
      (node (ref "RCAL_1") (pin "2") (pinfunction "2_2") (pintype "passive"))
      (node (ref "RCAL_2") (pin "1") (pinfunction "1_1") (pintype "passive"))
      (node (ref "STM32L432KC_CONN_") (pin "3.2") (pinfunction "PA10_3.2") (pintype "bidirectional"))
    )
    (net (code "27") (name "CAP1_VCF") (class "Default")
      (node (ref "C3") (pin "2") (pinfunction "2_2") (pintype "passive"))
      (node (ref "VCF") (pin "5") (pinfunction "CAP_5") (pintype "bidirectional"))
    )
    (net (code "28") (name "CAP2_VCF") (class "Default")
      (node (ref "C5") (pin "2") (pinfunction "2_2") (pintype "passive"))
      (node (ref "VCF") (pin "4") (pinfunction "CAP_4") (pintype "bidirectional"))
    )
    (net (code "29") (name "CAP3_VCF") (class "Default")
      (node (ref "C4") (pin "2") (pinfunction "2_2") (pintype "passive"))
      (node (ref "VCF") (pin "16") (pinfunction "CAP_16") (pintype "bidirectional"))
    )
    (net (code "30") (name "CAP4_VCF") (class "Default")
      (node (ref "C10") (pin "2") (pinfunction "2_2") (pintype "passive"))
      (node (ref "VCF") (pin "11") (pinfunction "CAP_11") (pintype "bidirectional"))
    )
    (net (code "31") (name "CV_CUTOFF") (class "Default")
      (node (ref "R2_VCF") (pin "2") (pinfunction "2_2") (pintype "passive"))
      (node (ref "U1") (pin "28") (pinfunction "VOUT_13_28") (pintype "tri_state"))
    )
    (net (code "32") (name "CV_FREQ_3340A") (class "Default")
      (node (ref "JP_FMLIN_VCO3340B1") (pin "1") (pinfunction "1_1") (pintype "passive"))
      (node (ref "R_CV_FREQ3") (pin "2") (pinfunction "2_2") (pintype "passive"))
      (node (ref "U1") (pin "12") (pinfunction "VOUT_3_12") (pintype "tri_state"))
    )
    (net (code "33") (name "CV_FREQ_3340B") (class "Default")
      (node (ref "R_CV_FREQ1") (pin "2") (pinfunction "2_2") (pintype "passive"))
      (node (ref "U1") (pin "9") (pinfunction "VOUT_0_9") (pintype "tri_state"))
    )
    (net (code "34") (name "CV_FREQ_13700") (class "Default")
      (node (ref "R1_EXPCONV2") (pin "2") (pinfunction "2_2") (pintype "passive"))
      (node (ref "TP_CV_2") (pin "P$1") (pinfunction "P$1_P$1") (pintype "passive"))
      (node (ref "U1") (pin "11") (pinfunction "VOUT_2_11") (pintype "tri_state"))
    )
    (net (code "35") (name "CV_PWM_3340A") (class "Default")
      (node (ref "3340A") (pin "5") (pinfunction "PWM_CTRL_5") (pintype "bidirectional"))
      (node (ref "R1_PWM3") (pin "1") (pinfunction "1_1") (pintype "passive"))
      (node (ref "R2_PWM3") (pin "1") (pinfunction "1_1") (pintype "passive"))
      (node (ref "U1") (pin "13") (pinfunction "VOUT_4_13") (pintype "tri_state"))
    )
    (net (code "36") (name "CV_PWM_3340B") (class "Default")
      (node (ref "3340B") (pin "5") (pinfunction "PWM_CTRL_5") (pintype "bidirectional"))
      (node (ref "R1_PWM1") (pin "1") (pinfunction "1_1") (pintype "passive"))
      (node (ref "R2_PWM1") (pin "1") (pinfunction "1_1") (pintype "passive"))
      (node (ref "U1") (pin "10") (pinfunction "VOUT_1_10") (pintype "tri_state"))
    )
    (net (code "37") (name "CV_RES") (class "Default")
      (node (ref "R_RES_VCF") (pin "2") (pinfunction "2_2") (pintype "passive"))
      (node (ref "U1") (pin "29") (pinfunction "VOUT_14_29") (pintype "tri_state"))
    )
    (net (code "38") (name "CV_VCA") (class "Default")
      (node (ref "RSTAB3_MIXERB1") (pin "1") (pinfunction "1_1") (pintype "passive"))
      (node (ref "U1") (pin "30") (pinfunction "VOUT_15_30") (pintype "tri_state"))
    )
    (net (code "39") (name "DAC_BUSY") (class "Default")
      (node (ref "STM32L432KC_CONN_") (pin "4.9") (pinfunction "PA4_4.9") (pintype "bidirectional"))
      (node (ref "U1") (pin "38") (pinfunction "~{BUSY}_38") (pintype "output"))
    )
    (net (code "40") (name "DAC_LDAC") (class "Default")
      (node (ref "STM32L432KC_CONN_") (pin "4.8") (pinfunction "PA5_4.8") (pintype "bidirectional"))
      (node (ref "U1") (pin "39") (pinfunction "~{LDAC}_39") (pintype "input"))
    )
    (net (code "41") (name "DAC_SYNC") (class "Default")
      (node (ref "STM32L432KC_CONN_") (pin "4.10") (pinfunction "PA3_4.10") (pintype "bidirectional"))
      (node (ref "U1") (pin "51") (pinfunction "~{SYNC}/AD0_51") (pintype "input"))
    )
    (net (code "42") (name "FM_ENTREE_13700_VCO13700") (class "Default")
      (node (ref "HEADER_EXPCONV2") (pin "3") (pinfunction "3_3") (pintype "passive"))
      (node (ref "RTEST_13700FREQ2") (pin "2") (pinfunction "2_2") (pintype "passive"))
      (node (ref "VCO2") (pin "1") (pinfunction "I_BIAS_1") (pintype "input"))
    )
    (net (code "43") (name "FREQ_CTRL_VCOA") (class "Default")
      (node (ref "3340A") (pin "15") (pinfunction "FREQ_CTRL_15") (pintype "bidirectional"))
      (node (ref "R_CV_FREQ3") (pin "1") (pinfunction "1_1") (pintype "passive"))
      (node (ref "R_CV_FREQ_BIAS3") (pin "1") (pinfunction "1_1") (pintype "passive"))
      (node (ref "R_CV_FREQ_STAB3") (pin "1") (pinfunction "1_1") (pintype "passive"))
    )
    (net (code "44") (name "FREQ_CTRL_VCOB") (class "Default")
      (node (ref "3340B") (pin "15") (pinfunction "FREQ_CTRL_15") (pintype "bidirectional"))
      (node (ref "R_CV_FREQ1") (pin "1") (pinfunction "1_1") (pintype "passive"))
      (node (ref "R_CV_FREQ_BIAS1") (pin "1") (pinfunction "1_1") (pintype "passive"))
      (node (ref "R_CV_FREQ_STAB1") (pin "1") (pinfunction "1_1") (pintype "passive"))
    )
    (net (code "45") (name "FREQ_CV_VCF") (class "Default")
      (node (ref "R1_VCF") (pin "1") (pinfunction "1_1") (pintype "passive"))
      (node (ref "R2_VCF") (pin "1") (pinfunction "1_1") (pintype "passive"))
      (node (ref "VCF") (pin "12") (pinfunction "FREQ_CV_12") (pintype "bidirectional"))
    )
    (net (code "46") (name "GAIN1_A") (class "Default")
      (node (ref "MIXER_A") (pin "3") (pinfunction "GAIN_VCA_3") (pintype "bidirectional"))
      (node (ref "U1") (pin "17") (pinfunction "VOUT_7_17") (pintype "tri_state"))
    )
    (net (code "47") (name "GAIN1_B") (class "Default")
      (node (ref "MIXER_B") (pin "3") (pinfunction "GAIN_VCA_3") (pintype "bidirectional"))
      (node (ref "U1") (pin "24") (pinfunction "VOUT_11_24") (pintype "tri_state"))
    )
    (net (code "48") (name "GAIN2_A") (class "Default")
      (node (ref "MIXER_A") (pin "6") (pinfunction "GAIN_VCA_6") (pintype "bidirectional"))
      (node (ref "U1") (pin "21") (pinfunction "VOUT_8_21") (pintype "tri_state"))
    )
    (net (code "49") (name "GAIN2_B") (class "Default")
      (node (ref "MIXER_B") (pin "6") (pinfunction "GAIN_VCA_6") (pintype "bidirectional"))
      (node (ref "U1") (pin "25") (pinfunction "VOUT_12_25") (pintype "tri_state"))
    )
    (net (code "50") (name "GAIN3_A") (class "Default")
      (node (ref "MIXER_A") (pin "11") (pinfunction "GAIN_VCA_11") (pintype "bidirectional"))
      (node (ref "U1") (pin "16") (pinfunction "VOUT_6_16") (pintype "tri_state"))
    )
    (net (code "51") (name "GAIN3_B") (class "Default")
      (node (ref "MIXER_B") (pin "11") (pinfunction "GAIN_VCA_11") (pintype "bidirectional"))
      (node (ref "U1") (pin "22") (pinfunction "VOUT_9_22") (pintype "tri_state"))
    )
    (net (code "52") (name "GAIN4_A") (class "Default")
      (node (ref "MIXER_A") (pin "14") (pinfunction "GAIN_VCA_14") (pintype "bidirectional"))
      (node (ref "U1") (pin "15") (pinfunction "VOUT_5_15") (pintype "tri_state"))
    )
    (net (code "53") (name "GAIN4_B") (class "Default")
      (node (ref "MIXER_B") (pin "14") (pinfunction "GAIN_VCA_14") (pintype "bidirectional"))
      (node (ref "U1") (pin "23") (pinfunction "VOUT_10_23") (pintype "tri_state"))
    )
    (net (code "54") (name "GPB_5") (class "Default")
      (node (ref "IC1") (pin "6") (pinfunction "GPB5_6") (pintype "bidirectional"))
    )
    (net (code "55") (name "GPB_6") (class "Default")
      (node (ref "IC1") (pin "7") (pinfunction "GPB6_7") (pintype "bidirectional"))
    )
    (net (code "56") (name "GPB_7") (class "Default")
      (node (ref "IC1") (pin "8") (pinfunction "GPB7_8") (pintype "bidirectional"))
    )
    (net (code "57") (name "HARD_SYNC_VCOA") (class "Default")
      (node (ref "3340A") (pin "6") (pinfunction "HARD_SYNC_6") (pintype "bidirectional"))
      (node (ref "C1_SYNC3") (pin "2") (pinfunction "2_2") (pintype "passive"))
    )
    (net (code "58") (name "HARD_SYNC_VCOB") (class "Default")
      (node (ref "3340B") (pin "6") (pinfunction "HARD_SYNC_6") (pintype "bidirectional"))
      (node (ref "C1_SYNC1") (pin "2") (pinfunction "2_2") (pintype "passive"))
    )
    (net (code "59") (name "IA_VCO13700") (class "Default")
      (node (ref "REE_2") (pin "1") (pinfunction "1_1") (pintype "passive"))
      (node (ref "VCO2") (pin "16") (pinfunction "I_BIAS_16") (pintype "input"))
    )
    (net (code "60") (name "IN1_MIXERA") (class "Default")
      (node (ref "CIN1_MIXERA") (pin "1") (pinfunction "1_1") (pintype "passive"))
      (node (ref "JP_TRIOUT_VCO3340B") (pin "2") (pinfunction "2_2") (pintype "passive"))
    )
    (net (code "61") (name "IN1_VCF") (class "Default")
      (node (ref "RC1_VCF") (pin "2") (pinfunction "2_2") (pintype "passive"))
      (node (ref "RF1_VCF") (pin "2") (pinfunction "2_2") (pintype "passive"))
      (node (ref "VCF") (pin "1") (pinfunction "IN_1") (pintype "bidirectional"))
    )
    (net (code "62") (name "IN2_MIXERA") (class "Default")
      (node (ref "CIN2_MIXERA") (pin "1") (pinfunction "1_1") (pintype "passive"))
      (node (ref "JP_OUT_VCO3340A") (pin "2") (pinfunction "2_2") (pintype "passive"))
      (node (ref "JP_OUT_VCO3340A2") (pin "1") (pinfunction "1_1") (pintype "passive"))
    )
    (net (code "63") (name "IN2_MIXERB") (class "Default")
      (node (ref "CIN2_MIXERB") (pin "1") (pinfunction "1_1") (pintype "passive"))
      (node (ref "JP8") (pin "2") (pinfunction "2_2") (pintype "passive"))
    )
    (net (code "64") (name "IN2_VCF") (class "Default")
      (node (ref "RB1_VCF") (pin "2") (pinfunction "2_2") (pintype "passive"))
      (node (ref "RC2_VCF") (pin "1") (pinfunction "1_1") (pintype "passive"))
      (node (ref "RF2_VCF") (pin "1") (pinfunction "1_1") (pintype "passive"))
      (node (ref "VCF") (pin "2") (pinfunction "IN_2") (pintype "bidirectional"))
    )
    (net (code "65") (name "IN3_MIXERA") (class "Default")
      (node (ref "CIN3_MIXERA") (pin "1") (pinfunction "1_1") (pintype "passive"))
      (node (ref "JP_SAWOUT_VCO3340B") (pin "2") (pinfunction "2_2") (pintype "passive"))
    )
    (net (code "66") (name "IN3_MIXERB") (class "Default")
      (node (ref "CIN3_MIXERB") (pin "1") (pinfunction "1_1") (pintype "passive"))
      (node (ref "JP9") (pin "2") (pinfunction "2_2") (pintype "passive"))
    )
    (net (code "67") (name "IN3_VCF") (class "Default")
      (node (ref "RB3_VCF") (pin "2") (pinfunction "2_2") (pintype "passive"))
      (node (ref "RC3") (pin "1") (pinfunction "1_1") (pintype "passive"))
      (node (ref "RF3") (pin "1") (pinfunction "1_1") (pintype "passive"))
      (node (ref "VCF") (pin "17") (pinfunction "IN_17") (pintype "bidirectional"))
    )
    (net (code "68") (name "IN4_MIXERA") (class "Default")
      (node (ref "CIN4_MIXERA") (pin "1") (pinfunction "1_1") (pintype "passive"))
      (node (ref "JP_PULSEOUT_VCO3340B") (pin "2") (pinfunction "2_2") (pintype "passive"))
    )
    (net (code "69") (name "IN4_MIXERB") (class "Default")
      (node (ref "CIN4_MIXERB") (pin "1") (pinfunction "1_1") (pintype "passive"))
      (node (ref "JP7") (pin "2") (pinfunction "2_2") (pintype "passive"))
    )
    (net (code "70") (name "IN4_VCF") (class "Default")
      (node (ref "RB2") (pin "2") (pinfunction "2_2") (pintype "passive"))
      (node (ref "RC4") (pin "1") (pinfunction "1_1") (pintype "passive"))
      (node (ref "RF4") (pin "1") (pinfunction "1_1") (pintype "passive"))
      (node (ref "VCF") (pin "18") (pinfunction "IN_18") (pintype "bidirectional"))
    )
    (net (code "71") (name "INPUT_CURRENT_SUM_STG") (class "Default")
      (node (ref "JP1") (pin "1") (pinfunction "1_1") (pintype "passive"))
      (node (ref "JP1") (pin "2") (pinfunction "2_2") (pintype "passive"))
      (node (ref "OPAMP_SUM_STG") (pin "2") (pinfunction "-IN_2") (pintype "input"))
      (node (ref "SUM_STG_C") (pin "2") (pinfunction "2_2") (pintype "passive"))
      (node (ref "SUM_STG_HEADER") (pin "1") (pinfunction "1_1") (pintype "passive"))
      (node (ref "SUM_STG_HEADER") (pin "2") (pinfunction "2_2") (pintype "passive"))
      (node (ref "SUM_STG_HEADER") (pin "3") (pinfunction "3_3") (pintype "passive"))
      (node (ref "SUM_STG_HEADER") (pin "4") (pinfunction "4_4") (pintype "passive"))
      (node (ref "SUM_STG_HEADER") (pin "5") (pinfunction "5_5") (pintype "passive"))
      (node (ref "SUM_STG_HEADER") (pin "6") (pinfunction "6_6") (pintype "passive"))
      (node (ref "SUM_STG_HEADER") (pin "7") (pinfunction "7_7") (pintype "passive"))
      (node (ref "SUM_STG_HEADER") (pin "8") (pinfunction "8_8") (pintype "passive"))
      (node (ref "SUM_STG_R") (pin "2") (pinfunction "2_2") (pintype "passive"))
      (node (ref "VCO1") (pin "5") (pinfunction "OUT_5") (pintype "output"))
    )
    (net (code "72") (name "INPUT_FM_3340") (class "Default")
      (node (ref "JP_OUT_VCO3340A1") (pin "2") (pinfunction "2_2") (pintype "passive"))
      (node (ref "RTEST_13700FREQ2") (pin "1") (pinfunction "1_1") (pintype "passive"))
    )
    (net (code "73") (name "IN_4THORDER") (class "Default")
      (node (ref "IC1") (pin "26") (pinfunction "GPA5_26") (pintype "bidirectional"))
    )
    (net (code "74") (name "IN_VCA") (class "Default")
      (node (ref "CSTAB1") (pin "2") (pinfunction "2_2") (pintype "passive"))
      (node (ref "VCF_JUMPER") (pin "2") (pinfunction "2_2") (pintype "passive"))
    )
    (net (code "75") (name "IN_VCF") (class "Default")
      (node (ref "C_IN2") (pin "2") (pinfunction "2_2") (pintype "passive"))
      (node (ref "VCF_JUMPER") (pin "4") (pinfunction "4_4") (pintype "passive"))
    )
    (net (code "76") (name "IN_VCFORDER") (class "Default")
      (node (ref "R_PD_4TH_ORDER_VCF") (pin "2") (pinfunction "2_2") (pintype "passive"))
      (node (ref "VCF_ANALOG_SW") (pin "1") (pinfunction "IN_1") (pintype "input"))
      (node (ref "VCF_ANALOG_SW") (pin "16") (pinfunction "IN_16") (pintype "input"))
    )
    (net (code "77") (name "JACK_SUM_STG") (class "Default")
      (node (ref "COUT_SUM_STG") (pin "-") (pinfunction "-_-") (pintype "passive"))
      (node (ref "JACK_SUM_STG") (pin "3") (pinfunction "2_3") (pintype "passive"))
    )
    (net (code "78") (name "LINEAR_CTRL_VCOA") (class "Default")
      (node (ref "3340A") (pin "13") (pinfunction "LINEAR_CTRL_13") (pintype "bidirectional"))
      (node (ref "R10_3") (pin "1") (pinfunction "1_1") (pintype "passive"))
      (node (ref "R8_3") (pin "1") (pinfunction "1_1") (pintype "passive"))
    )
    (net (code "79") (name "LINEAR_CTRL_VCOB") (class "Default")
      (node (ref "3340B") (pin "13") (pinfunction "LINEAR_CTRL_13") (pintype "bidirectional"))
      (node (ref "R10_1") (pin "1") (pinfunction "1_1") (pintype "passive"))
      (node (ref "R8_1") (pin "1") (pinfunction "1_1") (pintype "passive"))
    )
    (net (code "80") (name "N$4") (class "Default")
      (node (ref "JP_MIXER_A") (pin "4") (pinfunction "4_4") (pintype "passive"))
      (node (ref "MIXER_A") (pin "4") (pinfunction "I_OUT_4") (pintype "bidirectional"))
    )
    (net (code "81") (name "Net-(3A-D)") (class "Default")
      (node (ref "3") (pin "2") (pinfunction "D_2") (pintype "passive"))
      (node (ref "C1_1") (pin "2") (pinfunction "2_2") (pintype "passive"))
      (node (ref "R1_7") (pin "2") (pinfunction "2_2") (pintype "passive"))
    )
    (net (code "82") (name "Net-(3C-D)") (class "Default")
      (node (ref "3") (pin "10") (pinfunction "D_10") (pintype "passive"))
      (node (ref "C3_1") (pin "2") (pinfunction "2_2") (pintype "passive"))
      (node (ref "R3_4") (pin "2") (pinfunction "2_2") (pintype "passive"))
    )
    (net (code "83") (name "Net-(3D-D)") (class "Default")
      (node (ref "3") (pin "7") (pinfunction "D_7") (pintype "passive"))
      (node (ref "C2_1") (pin "2") (pinfunction "2_2") (pintype "passive"))
      (node (ref "R2_7") (pin "2") (pinfunction "2_2") (pintype "passive"))
    )
    (net (code "84") (name "Net-(3D-S)") (class "Default")
      (node (ref "3") (pin "6") (pinfunction "S_6") (pintype "passive"))
      (node (ref "R2S_1") (pin "2") (pinfunction "2_2") (pintype "passive"))
    )
    (net (code "85") (name "Net-(C1_SYNC1-Pad1)") (class "Default")
      (node (ref "C1_SYNC1") (pin "1") (pinfunction "1_1") (pintype "passive"))
      (node (ref "R_SYNC1") (pin "2") (pinfunction "2_2") (pintype "passive"))
    )
    (net (code "86") (name "Net-(C4_1-Pad1)") (class "Default")
      (node (ref "C4_1") (pin "1") (pinfunction "1_1") (pintype "passive"))
      (node (ref "R10_1") (pin "2") (pinfunction "2_2") (pintype "passive"))
    )
    (net (code "87") (name "Net-(C4_3-Pad1)") (class "Default")
      (node (ref "C4_3") (pin "1") (pinfunction "1_1") (pintype "passive"))
      (node (ref "R10_3") (pin "2") (pinfunction "2_2") (pintype "passive"))
    )
    (net (code "88") (name "Net-(CIN1_MIXERA-Pad2)") (class "Default")
      (node (ref "CIN1_MIXERA") (pin "2") (pinfunction "2_2") (pintype "passive"))
      (node (ref "RIN1_MIXERA") (pin "2") (pinfunction "2_2") (pintype "passive"))
    )
    (net (code "89") (name "Net-(CIN2_MIXERA-Pad2)") (class "Default")
      (node (ref "CIN2_MIXERA") (pin "2") (pinfunction "2_2") (pintype "passive"))
      (node (ref "RIN2_MIXERA") (pin "2") (pinfunction "2_2") (pintype "passive"))
    )
    (net (code "90") (name "Net-(CIN2_MIXERB-Pad2)") (class "Default")
      (node (ref "CIN2_MIXERB") (pin "2") (pinfunction "2_2") (pintype "passive"))
      (node (ref "RIN2_MIXERB") (pin "2") (pinfunction "2_2") (pintype "passive"))
    )
    (net (code "91") (name "Net-(CIN3_MIXERA-Pad2)") (class "Default")
      (node (ref "CIN3_MIXERA") (pin "2") (pinfunction "2_2") (pintype "passive"))
      (node (ref "RIN3_MIXERA") (pin "2") (pinfunction "2_2") (pintype "passive"))
    )
    (net (code "92") (name "Net-(CIN3_MIXERB-Pad2)") (class "Default")
      (node (ref "CIN3_MIXERB") (pin "2") (pinfunction "2_2") (pintype "passive"))
      (node (ref "RIN3_MIXERB") (pin "2") (pinfunction "2_2") (pintype "passive"))
    )
    (net (code "93") (name "Net-(CIN4_MIXERA-Pad2)") (class "Default")
      (node (ref "CIN4_MIXERA") (pin "2") (pinfunction "2_2") (pintype "passive"))
      (node (ref "RIN4_MIXERA") (pin "2") (pinfunction "2_2") (pintype "passive"))
    )
    (net (code "94") (name "Net-(CIN4_MIXERB-Pad2)") (class "Default")
      (node (ref "CIN4_MIXERB") (pin "2") (pinfunction "2_2") (pintype "passive"))
      (node (ref "RIN4_MIXERB") (pin "2") (pinfunction "2_2") (pintype "passive"))
    )
    (net (code "95") (name "Net-(CIN4_MIXERB1-Pad1)") (class "Default")
      (node (ref "CIN4_MIXERB1") (pin "1") (pinfunction "1_1") (pintype "passive"))
      (node (ref "JP_OUT_VCO3340A2") (pin "2") (pinfunction "2_2") (pintype "passive"))
    )
    (net (code "96") (name "Net-(CIN4_MIXERB1-Pad2)") (class "Default")
      (node (ref "CIN4_MIXERB1") (pin "2") (pinfunction "2_2") (pintype "passive"))
      (node (ref "RIN4_MIXERB1") (pin "2") (pinfunction "2_2") (pintype "passive"))
    )
    (net (code "97") (name "Net-(CONVLOG2-C1)") (class "Default")
      (node (ref "CONVLOG2") (pin "6") (pinfunction "C1_6") (pintype "passive"))
      (node (ref "EXPCONV2") (pin "2") (pinfunction "-IN_2") (pintype "input"))
      (node (ref "RBIAS_EXPCONV2") (pin "2") (pinfunction "2_2") (pintype "passive"))
    )
    (net (code "98") (name "Net-(CONVLOG2-E1)") (class "Default")
      (node (ref "CONVLOG2") (pin "1") (pinfunction "E1_1") (pintype "passive"))
      (node (ref "CONVLOG2") (pin "4") (pinfunction "E2_4") (pintype "passive"))
      (node (ref "R5_EXPCONV2") (pin "1") (pinfunction "1_1") (pintype "passive"))
    )
    (net (code "99") (name "Net-(CONV_ITOV_OUT--IN)") (class "Default")
      (node (ref "CONV_ITOV_OUT") (pin "2") (pinfunction "-IN_2") (pintype "input"))
      (node (ref "C_CONV_ITOV_OUT") (pin "1") (pinfunction "1_1") (pintype "passive"))
      (node (ref "JP_MIXER_A") (pin "1") (pinfunction "1_1") (pintype "passive"))
      (node (ref "JP_MIXER_A") (pin "3") (pinfunction "3_3") (pintype "passive"))
      (node (ref "JP_MIXER_A") (pin "5") (pinfunction "5_5") (pintype "passive"))
      (node (ref "JP_MIXER_A") (pin "7") (pinfunction "7_7") (pintype "passive"))
      (node (ref "JP_MIXER_B") (pin "1") (pinfunction "1_1") (pintype "passive"))
      (node (ref "JP_MIXER_B") (pin "3") (pinfunction "3_3") (pintype "passive"))
      (node (ref "JP_MIXER_B") (pin "5") (pinfunction "5_5") (pintype "passive"))
      (node (ref "JP_MIXER_B") (pin "7") (pinfunction "7_7") (pintype "passive"))
      (node (ref "R_CONV_ITOV_OUT") (pin "1") (pinfunction "1_1") (pintype "passive"))
    )
    (net (code "100") (name "Net-(CSTAB1_MIXERA-Pad2)") (class "Default")
      (node (ref "CSTAB1_MIXERA") (pin "2") (pinfunction "2_2") (pintype "passive"))
      (node (ref "RSTAB1_MIXERA") (pin "2") (pinfunction "2_2") (pintype "passive"))
    )
    (net (code "101") (name "Net-(CSTAB2-Pad1)") (class "Default")
      (node (ref "CSTAB2") (pin "1") (pinfunction "1_1") (pintype "passive"))
      (node (ref "JP_OUT_VCO3340A1") (pin "1") (pinfunction "1_1") (pintype "passive"))
    )
    (net (code "102") (name "Net-(CSTAB2_MIXERA-Pad2)") (class "Default")
      (node (ref "CSTAB2_MIXERA") (pin "2") (pinfunction "2_2") (pintype "passive"))
      (node (ref "RSTAB2_MIXERA") (pin "2") (pinfunction "2_2") (pintype "passive"))
    )
    (net (code "103") (name "Net-(CSTAB2_MIXERB-Pad2)") (class "Default")
      (node (ref "CSTAB2_MIXERB") (pin "2") (pinfunction "2_2") (pintype "passive"))
      (node (ref "RSTAB2_MIXERB") (pin "2") (pinfunction "2_2") (pintype "passive"))
    )
    (net (code "104") (name "Net-(CSTAB3-Pad2)") (class "Default")
      (node (ref "CSTAB3") (pin "2") (pinfunction "2_2") (pintype "passive"))
      (node (ref "RSTAB4_MIXERB2") (pin "2") (pinfunction "2_2") (pintype "passive"))
    )
    (net (code "105") (name "Net-(CSTAB3_MIXERA-Pad2)") (class "Default")
      (node (ref "CSTAB3_MIXERA") (pin "2") (pinfunction "2_2") (pintype "passive"))
      (node (ref "RSTAB3_MIXERA") (pin "2") (pinfunction "2_2") (pintype "passive"))
    )
    (net (code "106") (name "Net-(CSTAB3_MIXERB-Pad2)") (class "Default")
      (node (ref "CSTAB3_MIXERB") (pin "2") (pinfunction "2_2") (pintype "passive"))
      (node (ref "RSTAB3_MIXERB") (pin "2") (pinfunction "2_2") (pintype "passive"))
    )
    (net (code "107") (name "Net-(CSTAB4_MIXERA-Pad2)") (class "Default")
      (node (ref "CSTAB4_MIXERA") (pin "2") (pinfunction "2_2") (pintype "passive"))
      (node (ref "RSTAB4_MIXERA") (pin "2") (pinfunction "2_2") (pintype "passive"))
    )
    (net (code "108") (name "Net-(CSTAB8-Pad2)") (class "Default")
      (node (ref "CSTAB8") (pin "2") (pinfunction "2_2") (pintype "passive"))
      (node (ref "RSTAB4_MIXERB") (pin "2") (pinfunction "2_2") (pintype "passive"))
    )
    (net (code "109") (name "Net-(C_CV_FREQ_STAB1-Pad2)") (class "Default")
      (node (ref "C_CV_FREQ_STAB1") (pin "2") (pinfunction "2_2") (pintype "passive"))
      (node (ref "R_CV_FREQ_STAB1") (pin "2") (pinfunction "2_2") (pintype "passive"))
    )
    (net (code "110") (name "Net-(C_CV_FREQ_STAB3-Pad2)") (class "Default")
      (node (ref "C_CV_FREQ_STAB3") (pin "2") (pinfunction "2_2") (pintype "passive"))
      (node (ref "R_CV_FREQ_STAB3") (pin "2") (pinfunction "2_2") (pintype "passive"))
    )
    (net (code "111") (name "Net-(C_IN2-Pad1)") (class "Default")
      (node (ref "C_IN2") (pin "1") (pinfunction "1_1") (pintype "passive"))
      (node (ref "RC1_VCF") (pin "1") (pinfunction "1_1") (pintype "passive"))
    )
    (net (code "112") (name "Net-(D_2-PadC)") (class "Default")
      (node (ref "D_2") (pin "C") (pinfunction "C_C") (pintype "passive"))
      (node (ref "R_LIM_2") (pin "2") (pinfunction "2_2") (pintype "passive"))
    )
    (net (code "113") (name "Net-(EXPCONV2-OUT)") (class "Default")
      (node (ref "EXPCONV2") (pin "6") (pinfunction "OUT_6") (pintype "output"))
      (node (ref "R5_EXPCONV2") (pin "2") (pinfunction "2_2") (pintype "passive"))
    )
    (net (code "114") (name "Net-(HEADER_EXPCONV2-Pad1)") (class "Default")
      (node (ref "HEADER_EXPCONV2") (pin "1") (pinfunction "1_1") (pintype "passive"))
      (node (ref "RTEST_LOG2") (pin "1") (pinfunction "1_1") (pintype "passive"))
    )
    (net (code "115") (name "Net-(MIXER_BB-I_IN)") (class "Default")
      (node (ref "MIXER_B") (pin "2") (pinfunction "I_IN_2") (pintype "bidirectional"))
      (node (ref "RIN4_MIXERB1") (pin "1") (pinfunction "1_1") (pintype "passive"))
      (node (ref "RSTAB4_MIXERB2") (pin "1") (pinfunction "1_1") (pintype "passive"))
    )
    (net (code "116") (name "Net-(MIXER_BB-I_OUT)") (class "Default")
      (node (ref "CSTAB2") (pin "2") (pinfunction "2_2") (pintype "passive"))
      (node (ref "MIXER_B") (pin "4") (pinfunction "I_OUT_4") (pintype "bidirectional"))
      (node (ref "RSTAB4_MIXERB1") (pin "2") (pinfunction "2_2") (pintype "passive"))
    )
    (net (code "117") (name "Net-(MIXER_BE-I_OUT)") (class "Default")
      (node (ref "JP_MIXER_B") (pin "8") (pinfunction "8_8") (pintype "passive"))
      (node (ref "MIXER_B") (pin "12") (pinfunction "I_OUT_12") (pintype "bidirectional"))
    )
    (net (code "118") (name "Net-(S1-P)") (class "Default")
      (node (ref "R_SW1A") (pin "2") (pinfunction "2_2") (pintype "passive"))
      (node (ref "R_SW1B") (pin "1") (pinfunction "1_1") (pintype "passive"))
      (node (ref "S1") (pin "3") (pinfunction "P_3") (pintype "passive"))
      (node (ref "S1") (pin "4") (pinfunction "P1_4") (pintype "passive"))
    )
    (net (code "119") (name "Net-(S2-P)") (class "Default")
      (node (ref "R_SW2A") (pin "2") (pinfunction "2_2") (pintype "passive"))
      (node (ref "R_SW2B") (pin "1") (pinfunction "1_1") (pintype "passive"))
      (node (ref "S2") (pin "3") (pinfunction "P_3") (pintype "passive"))
      (node (ref "S2") (pin "4") (pinfunction "P1_4") (pintype "passive"))
    )
    (net (code "120") (name "Net-(SUBBASS2-1J)") (class "Default")
      (node (ref "SUBBASS2") (pin "10") (pinfunction "1J_10") (pintype "input"))
      (node (ref "SUBBASS2") (pin "14") (pinfunction "1~{Q}_14") (pintype "output"))
    )
    (net (code "121") (name "Net-(VCF_ANALOG_SWA-S)") (class "Default")
      (node (ref "CRES_VCF") (pin "1") (pinfunction "1_1") (pintype "passive"))
      (node (ref "VCF_ANALOG_SW") (pin "14") (pinfunction "S_14") (pintype "bidirectional"))
      (node (ref "VCF_ANALOG_SW") (pin "3") (pinfunction "S_3") (pintype "bidirectional"))
    )
    (net (code "122") (name "Net-(VCO1C-IN_N)") (class "Default")
      (node (ref "RSTAB3_MIXERB4") (pin "2") (pinfunction "2_2") (pintype "passive"))
      (node (ref "RSTAB3_MIXERB5") (pin "2") (pinfunction "2_2") (pintype "passive"))
      (node (ref "VCO1") (pin "4") (pinfunction "IN_N_4") (pintype "input"))
    )
    (net (code "123") (name "Net-(VCO1C-IN_P)") (class "Default")
      (node (ref "CSTAB1") (pin "1") (pinfunction "1_1") (pintype "passive"))
      (node (ref "RSTAB3_MIXERB2") (pin "2") (pinfunction "2_2") (pintype "passive"))
      (node (ref "RSTAB3_MIXERB3") (pin "1") (pinfunction "1_1") (pintype "passive"))
      (node (ref "VCO1") (pin "3") (pinfunction "IN_P_3") (pintype "input"))
    )
    (net (code "124") (name "Net-(VCO1C-I_BIAS)") (class "Default")
      (node (ref "RSTAB3_MIXERB1") (pin "2") (pinfunction "2_2") (pintype "passive"))
      (node (ref "VCO1") (pin "1") (pinfunction "I_BIAS_1") (pintype "input"))
    )
    (net (code "125") (name "Net-(VCO2A-B)") (class "Default")
      (node (ref "CF_2") (pin "2") (pinfunction "2_2") (pintype "passive"))
      (node (ref "VCO2") (pin "5") (pinfunction "OUT_5") (pintype "output"))
      (node (ref "VCO2") (pin "7") (pinfunction "B_7") (pintype "passive"))
    )
    (net (code "126") (name "Net-(VCO2B-B)") (class "Default")
      (node (ref "RA_2") (pin "2") (pinfunction "2_2") (pintype "passive"))
      (node (ref "VCO2") (pin "10") (pinfunction "B_10") (pintype "passive"))
      (node (ref "VCO2") (pin "12") (pinfunction "OUT_12") (pintype "output"))
      (node (ref "VCO2") (pin "14") (pinfunction "IN_P_14") (pintype "input"))
      (node (ref "VCO2") (pin "3") (pinfunction "IN_P_3") (pintype "input"))
    )
    (net (code "127") (name "OUT1_VCF") (class "Default")
      (node (ref "RC2_VCF") (pin "2") (pinfunction "2_2") (pintype "passive"))
      (node (ref "RF1_VCF") (pin "1") (pinfunction "1_1") (pintype "passive"))
      (node (ref "VCF") (pin "7") (pinfunction "OUT_7") (pintype "bidirectional"))
    )
    (net (code "128") (name "OUT2_VCF") (class "Default")
      (node (ref "RC3") (pin "2") (pinfunction "2_2") (pintype "passive"))
      (node (ref "RF2_VCF") (pin "2") (pinfunction "2_2") (pintype "passive"))
      (node (ref "VCF") (pin "6") (pinfunction "OUT_6") (pintype "bidirectional"))
      (node (ref "VCF_ANALOG_SW") (pin "15") (pinfunction "D_15") (pintype "bidirectional"))
    )
    (net (code "129") (name "OUT3_VCF") (class "Default")
      (node (ref "RC4") (pin "2") (pinfunction "2_2") (pintype "passive"))
      (node (ref "RF3") (pin "2") (pinfunction "2_2") (pintype "passive"))
      (node (ref "VCF") (pin "15") (pinfunction "OUT_15") (pintype "bidirectional"))
    )
    (net (code "130") (name "OUT4_VCF") (class "Default")
      (node (ref "RF4") (pin "2") (pinfunction "2_2") (pintype "passive"))
      (node (ref "VCF") (pin "10") (pinfunction "OUT_10") (pintype "bidirectional"))
      (node (ref "VCF_ANALOG_SW") (pin "2") (pinfunction "D_2") (pintype "bidirectional"))
    )
    (net (code "131") (name "OUT_EXPCONV_VCO13700") (class "Default")
      (node (ref "CONVLOG2") (pin "3") (pinfunction "C2_3") (pintype "passive"))
      (node (ref "HEADER_EXPCONV2") (pin "2") (pinfunction "2_2") (pintype "passive"))
    )
    (net (code "132") (name "OUT_MIXER") (class "Default")
      (node (ref "CONV_ITOV_OUT") (pin "6") (pinfunction "OUT_6") (pintype "output"))
      (node (ref "C_CONV_ITOV_OUT") (pin "2") (pinfunction "2_2") (pintype "passive"))
      (node (ref "R_CONV_ITOV_OUT") (pin "2") (pinfunction "2_2") (pintype "passive"))
      (node (ref "VCF_JUMPER") (pin "3") (pinfunction "3_3") (pintype "passive"))
    )
    (net (code "133") (name "OUT_SUM_STG") (class "Default")
      (node (ref "OPAMP_SUM_STG") (pin "6") (pinfunction "OUT_6") (pintype "output"))
      (node (ref "ROUT_SUM_STG") (pin "2") (pinfunction "2_2") (pintype "passive"))
      (node (ref "SUM_STG_C") (pin "1") (pinfunction "1_1") (pintype "passive"))
      (node (ref "SUM_STG_R") (pin "1") (pinfunction "1_1") (pintype "passive"))
    )
    (net (code "134") (name "OUT_VCF") (class "Default")
      (node (ref "CRES_VCF") (pin "2") (pinfunction "2_2") (pintype "passive"))
      (node (ref "RRI_VCF") (pin "2") (pinfunction "2_2") (pintype "passive"))
      (node (ref "VCF_JUMPER") (pin "1") (pinfunction "1_1") (pintype "passive"))
    )
    (net (code "135") (name "PNP1_B_VCO13700") (class "Default")
      (node (ref "CONVLOG2") (pin "2") (pinfunction "B1_2") (pintype "passive"))
      (node (ref "R1_EXPCONV2") (pin "1") (pinfunction "1_1") (pintype "passive"))
      (node (ref "R2_EXPCONV2") (pin "1") (pinfunction "1_1") (pintype "passive"))
    )
    (net (code "136") (name "PNP2_B_VCO13700") (class "Default")
      (node (ref "CONVLOG2") (pin "5") (pinfunction "B2_5") (pintype "passive"))
      (node (ref "R3_EXPCONV2") (pin "1") (pinfunction "1_1") (pintype "passive"))
      (node (ref "R4_EXPCONV2") (pin "1") (pinfunction "1_1") (pintype "passive"))
    )
    (net (code "137") (name "POT2_SUM_STG") (class "Default")
      (node (ref "COUT_SUM_STG") (pin "+") (pinfunction "+_+") (pintype "passive"))
      (node (ref "POT_SUM_STG") (pin "2") (pinfunction "S_2") (pintype "passive"))
    )
    (net (code "138") (name "POT3_SUM_STG") (class "Default")
      (node (ref "POT_SUM_STG") (pin "3") (pinfunction "E_3") (pintype "passive"))
      (node (ref "ROUT_SUM_STG") (pin "1") (pinfunction "1_1") (pintype "passive"))
    )
    (net (code "139") (name "PULSE_OUT_VCOA") (class "Default")
      (node (ref "3") (pin "11") (pinfunction "S_11") (pintype "passive"))
      (node (ref "R3S_1") (pin "2") (pinfunction "2_2") (pintype "passive"))
    )
    (net (code "140") (name "PULSE_VCOA") (class "Default")
      (node (ref "3340A") (pin "4") (pinfunction "PULSE_OUT_4") (pintype "bidirectional"))
      (node (ref "C3_1") (pin "1") (pinfunction "1_1") (pintype "passive"))
      (node (ref "R6_3") (pin "2") (pinfunction "2_2") (pintype "passive"))
      (node (ref "TP_PULSE3") (pin "P$1") (pinfunction "P$1_P$1") (pintype "passive"))
    )
    (net (code "141") (name "REFOUT") (class "Default")
      (node (ref "CDEC_VREF") (pin "1") (pinfunction "1_1") (pintype "passive"))
      (node (ref "U1") (pin "5") (pinfunction "REFOUT/REFIN_5") (pintype "bidirectional"))
    )
    (net (code "142") (name "RES_CUR_IN_VCF") (class "Default")
      (node (ref "RRI_VCF") (pin "1") (pinfunction "1_1") (pintype "passive"))
      (node (ref "VCF") (pin "8") (pinfunction "IN_RES_8") (pintype "bidirectional"))
    )
    (net (code "143") (name "RES_CUR_VCF") (class "Default")
      (node (ref "R_RES_VCF") (pin "1") (pinfunction "1_1") (pintype "passive"))
      (node (ref "VCF") (pin "9") (pinfunction "RES_CUR_9") (pintype "bidirectional"))
    )
    (net (code "144") (name "RST") (class "Default")
      (node (ref "IC1") (pin "18") (pinfunction "~{RESET}_18") (pintype "input"))
      (node (ref "R_RST") (pin "2") (pinfunction "2_2") (pintype "passive"))
      (node (ref "STM32L432KC_CONN_") (pin "3.6") (pinfunction "PB0_3.6") (pintype "bidirectional"))
      (node (ref "U1") (pin "37") (pinfunction "~{RESET}_37") (pintype "input"))
    )
    (net (code "145") (name "SAW_3340_VCOA") (class "Default")
      (node (ref "C2_1") (pin "1") (pinfunction "1_1") (pintype "passive"))
      (node (ref "R7_3") (pin "1") (pinfunction "1_1") (pintype "passive"))
      (node (ref "TP_SAW3") (pin "P$1") (pinfunction "P$1_P$1") (pintype "passive"))
    )
    (net (code "146") (name "SAW_VCOA") (class "Default")
      (node (ref "3340A") (pin "8") (pinfunction "SAW_OUT_8") (pintype "bidirectional"))
      (node (ref "R7_3") (pin "2") (pinfunction "2_2") (pintype "passive"))
    )
    (net (code "147") (name "SAW_VCOB") (class "Default")
      (node (ref "3340B") (pin "8") (pinfunction "SAW_OUT_8") (pintype "bidirectional"))
      (node (ref "R7_1") (pin "2") (pinfunction "2_2") (pintype "passive"))
    )
    (net (code "148") (name "SCALE_VCOA") (class "Default")
      (node (ref "3340A") (pin "14") (pinfunction "SCALE_14") (pintype "bidirectional"))
      (node (ref "R11_3") (pin "1") (pinfunction "1_1") (pintype "passive"))
    )
    (net (code "149") (name "SCALE_VCOB") (class "Default")
      (node (ref "3340B") (pin "14") (pinfunction "SCALE_14") (pintype "bidirectional"))
      (node (ref "R11_1") (pin "1") (pinfunction "1_1") (pintype "passive"))
    )
    (net (code "150") (name "SCL") (class "Default")
      (node (ref "IC1") (pin "12") (pinfunction "SCL_12") (pintype "input"))
      (node (ref "IC_EEPROM") (pin "6") (pinfunction "SCL_6") (pintype "input"))
      (node (ref "STM32L432KC_CONN_") (pin "4.6") (pinfunction "PA7_4.6") (pintype "bidirectional"))
    )
    (net (code "151") (name "SDA") (class "Default")
      (node (ref "IC1") (pin "13") (pinfunction "SDA_13") (pintype "bidirectional"))
      (node (ref "IC_EEPROM") (pin "5") (pinfunction "SDA_5") (pintype "bidirectional"))
      (node (ref "STM32L432KC_CONN_") (pin "3.15") (pinfunction "PB4_3.15") (pintype "bidirectional"))
    )
    (net (code "152") (name "SOFT_SYNC_VCOA") (class "Default")
      (node (ref "3340A") (pin "9") (pinfunction "SOFT_SYNC_9") (pintype "bidirectional"))
      (node (ref "C2_SYNC3") (pin "2") (pinfunction "2_2") (pintype "passive"))
    )
    (net (code "153") (name "SOFT_SYNC_VCOB") (class "Default")
      (node (ref "3340B") (pin "9") (pinfunction "SOFT_SYNC_9") (pintype "bidirectional"))
      (node (ref "C2_SYNC1") (pin "2") (pinfunction "2_2") (pintype "passive"))
    )
    (net (code "154") (name "SPI_CLK") (class "Default")
      (node (ref "STM32L432KC_CONN_") (pin "4.11") (pinfunction "PA1_4.11") (pintype "bidirectional"))
      (node (ref "U1") (pin "49") (pinfunction "SCLK/SCL_49") (pintype "input"))
    )
    (net (code "155") (name "SPI_MISO") (class "Default")
      (node (ref "STM32L432KC_CONN_") (pin "4.7") (pinfunction "PA6_4.7") (pintype "bidirectional"))
      (node (ref "U1") (pin "48") (pinfunction "SDO_48") (pintype "tri_state"))
    )
    (net (code "156") (name "SPI_MOSI") (class "Default")
      (node (ref "STM32L432KC_CONN_") (pin "3.5") (pinfunction "PA12_3.5") (pintype "bidirectional"))
      (node (ref "U1") (pin "50") (pinfunction "DIN/SDA_50") (pintype "bidirectional"))
    )
    (net (code "157") (name "SUBBASS_IN_VCO13700") (class "Default")
      (node (ref "R_LIM_2") (pin "1") (pinfunction "1_1") (pintype "passive"))
      (node (ref "SUBBASS2") (pin "13") (pinfunction "1CP_13") (pintype "input"))
    )
    (net (code "158") (name "SW1") (class "Default")
      (node (ref "C_SW1") (pin "1") (pinfunction "1_1") (pintype "passive"))
      (node (ref "R_SW1B") (pin "2") (pinfunction "2_2") (pintype "passive"))
      (node (ref "STM32L432KC_CONN_") (pin "3.14") (pinfunction "PB5_3.14") (pintype "bidirectional"))
    )
    (net (code "159") (name "SW2") (class "Default")
      (node (ref "C_SW2") (pin "1") (pinfunction "1_1") (pintype "passive"))
      (node (ref "R_SW2B") (pin "2") (pinfunction "2_2") (pintype "passive"))
      (node (ref "STM32L432KC_CONN_") (pin "3.13") (pinfunction "PA11_3.13") (pintype "bidirectional"))
    )
    (net (code "160") (name "SYNC_3340_VCOA") (class "Default")
      (node (ref "3") (pin "15") (pinfunction "D_15") (pintype "passive"))
      (node (ref "C1_SYNC3") (pin "1") (pinfunction "1_1") (pintype "passive"))
      (node (ref "R_SYNC3") (pin "2") (pinfunction "2_2") (pintype "passive"))
    )
    (net (code "161") (name "SYNC_IN_VCOA") (class "Default")
      (node (ref "3") (pin "14") (pinfunction "S_14") (pintype "passive"))
      (node (ref "JP_SYNC_3340B_TO_A") (pin "1") (pinfunction "1_1") (pintype "passive"))
    )
    (net (code "162") (name "TEMPCO1_VCOA") (class "Default")
      (node (ref "3340A") (pin "1") (pinfunction "MUL_GAIN1_1") (pintype "bidirectional"))
      (node (ref "R1_4") (pin "1") (pinfunction "1_1") (pintype "passive"))
    )
    (net (code "163") (name "TEMPCO1_VCOB") (class "Default")
      (node (ref "3340B") (pin "1") (pinfunction "MUL_GAIN1_1") (pintype "bidirectional"))
      (node (ref "R1_3") (pin "1") (pinfunction "1_1") (pintype "passive"))
    )
    (net (code "164") (name "TEMPCO2_VCOA") (class "Default")
      (node (ref "3340A") (pin "2") (pinfunction "MUL_GAIN2_2") (pintype "bidirectional"))
      (node (ref "R2_4") (pin "1") (pinfunction "1_1") (pintype "passive"))
    )
    (net (code "165") (name "TEMPCO2_VCOB") (class "Default")
      (node (ref "3340B") (pin "2") (pinfunction "MUL_GAIN2_2") (pintype "bidirectional"))
      (node (ref "R2_3") (pin "1") (pinfunction "1_1") (pintype "passive"))
    )
    (net (code "166") (name "TIMING_CAP_VCOA") (class "Default")
      (node (ref "3340A") (pin "11") (pinfunction "TIMING_CAP_11") (pintype "bidirectional"))
      (node (ref "C_3") (pin "2") (pinfunction "2_2") (pintype "passive"))
    )
    (net (code "167") (name "TIMING_CAP_VCOB") (class "Default")
      (node (ref "3340B") (pin "11") (pinfunction "TIMING_CAP_11") (pintype "bidirectional"))
      (node (ref "C_1") (pin "2") (pinfunction "2_2") (pintype "passive"))
    )
    (net (code "168") (name "TRI_3340_VCOA") (class "Default")
      (node (ref "3340A") (pin "10") (pinfunction "TRI_OUT_10") (pintype "bidirectional"))
      (node (ref "C1_1") (pin "1") (pinfunction "1_1") (pintype "passive"))
      (node (ref "TP_TRI3") (pin "P$1") (pinfunction "P$1_P$1") (pintype "passive"))
    )
    (net (code "169") (name "TRI_OUT_VCOA") (class "Default")
      (node (ref "3") (pin "3") (pinfunction "S_3") (pintype "passive"))
      (node (ref "R1S_1") (pin "1") (pinfunction "1_1") (pintype "passive"))
    )
    (net (code "170") (name "USART_RX_RPI_TX") (class "Default")
      (node (ref "CONN_UART_RPI") (pin "2") (pinfunction "2_2") (pintype "passive"))
      (node (ref "STM32L432KC_CONN_") (pin "3.7") (pinfunction "PB7_3.7") (pintype "bidirectional"))
    )
    (net (code "171") (name "USART_TX_RPI_RX") (class "Default")
      (node (ref "CONN_UART_RPI") (pin "3") (pinfunction "3_3") (pintype "passive"))
      (node (ref "STM32L432KC_CONN_") (pin "3.8") (pinfunction "PB6_3.8") (pintype "bidirectional"))
    )
    (net (code "172") (name "VCO440A_OUT") (class "Default")
      (node (ref "JP_OUT_VCO3340A") (pin "1") (pinfunction "1_1") (pintype "passive"))
      (node (ref "R1S_1") (pin "2") (pinfunction "2_2") (pintype "passive"))
      (node (ref "R2S_1") (pin "1") (pinfunction "1_1") (pintype "passive"))
      (node (ref "R3S_1") (pin "1") (pinfunction "1_1") (pintype "passive"))
    )
    (net (code "173") (name "VCO3340B_PULSE_OUT") (class "Default")
      (node (ref "3340B") (pin "4") (pinfunction "PULSE_OUT_4") (pintype "bidirectional"))
      (node (ref "JP_PULSEOUT_VCO3340B") (pin "1") (pinfunction "1_1") (pintype "passive"))
      (node (ref "R6_1") (pin "2") (pinfunction "2_2") (pintype "passive"))
      (node (ref "TP_PULSE1") (pin "P$1") (pinfunction "P$1_P$1") (pintype "passive"))
    )
    (net (code "174") (name "VCO3340B_SAW_OUT") (class "Default")
      (node (ref "JP_SAWOUT_VCO3340B") (pin "1") (pinfunction "1_1") (pintype "passive"))
      (node (ref "JP_SYNC_3340B_TO_A") (pin "2") (pinfunction "2_2") (pintype "passive"))
      (node (ref "R7_1") (pin "1") (pinfunction "1_1") (pintype "passive"))
      (node (ref "TP_SAW1") (pin "P$1") (pinfunction "P$1_P$1") (pintype "passive"))
    )
    (net (code "175") (name "VCO3340B_TRI_OUT") (class "Default")
      (node (ref "3340B") (pin "10") (pinfunction "TRI_OUT_10") (pintype "bidirectional"))
      (node (ref "JP_TRIOUT_VCO3340B") (pin "1") (pinfunction "1_1") (pintype "passive"))
      (node (ref "TP_TRI1") (pin "P$1") (pinfunction "P$1_P$1") (pintype "passive"))
    )
    (net (code "176") (name "VCO13700_SQUARE") (class "Default")
      (node (ref "CIN_2") (pin "2") (pinfunction "2_2") (pintype "passive"))
      (node (ref "JP8") (pin "1") (pinfunction "1_1") (pintype "passive"))
      (node (ref "RSQU_2") (pin "2") (pinfunction "2_2") (pintype "passive"))
      (node (ref "TP_13700_SQU2") (pin "P$1") (pinfunction "P$1_P$1") (pintype "passive"))
      (node (ref "VCO2") (pin "9") (pinfunction "E_9") (pintype "passive"))
    )
    (net (code "177") (name "VCO13700_SUBBASS") (class "Default")
      (node (ref "JP7") (pin "1") (pinfunction "1_1") (pintype "passive"))
      (node (ref "RCAL_1") (pin "1") (pinfunction "1_1") (pintype "passive"))
      (node (ref "SUBBASS2") (pin "15") (pinfunction "1Q_15") (pintype "output"))
    )
    (net (code "178") (name "VCO13700_TRI") (class "Default")
      (node (ref "JP9") (pin "1") (pinfunction "1_1") (pintype "passive"))
      (node (ref "RTRI_2") (pin "2") (pinfunction "2_2") (pintype "passive"))
      (node (ref "TP_13700_TRI2") (pin "P$1") (pinfunction "P$1_P$1") (pintype "passive"))
      (node (ref "VCO2") (pin "13") (pinfunction "IN_N_13") (pintype "input"))
      (node (ref "VCO2") (pin "8") (pinfunction "E_8") (pintype "passive"))
    )
    (net (code "179") (name "VEE_VCF") (class "Default")
      (node (ref "C-15VPOL_VCF") (pin "1") (pinfunction "1_1") (pintype "passive"))
      (node (ref "C-15V_VCF") (pin "1") (pinfunction "1_1") (pintype "passive"))
      (node (ref "REE_VCF") (pin "2") (pinfunction "2_2") (pintype "passive"))
      (node (ref "VCF") (pin "13") (pinfunction "V-_13") (pintype "bidirectional"))
    )
    (net (code "180") (name "VEE_VCOA") (class "Default")
      (node (ref "3340A") (pin "3") (pinfunction "VEE_3") (pintype "bidirectional"))
      (node (ref "CDEC_3340B6") (pin "2") (pinfunction "2_2") (pintype "passive"))
      (node (ref "CDEC_3340B7") (pin "2") (pinfunction "2_2") (pintype "passive"))
      (node (ref "R1_4") (pin "2") (pinfunction "2_2") (pintype "passive"))
      (node (ref "R2_4") (pin "2") (pinfunction "2_2") (pintype "passive"))
      (node (ref "R3_3") (pin "2") (pinfunction "2_2") (pintype "passive"))
    )
    (net (code "181") (name "VEE_VCOB") (class "Default")
      (node (ref "3340B") (pin "3") (pinfunction "VEE_3") (pintype "bidirectional"))
      (node (ref "CDEC_3340B2") (pin "2") (pinfunction "2_2") (pintype "passive"))
      (node (ref "CDEC_3340B3") (pin "2") (pinfunction "2_2") (pintype "passive"))
      (node (ref "R1_3") (pin "2") (pinfunction "2_2") (pintype "passive"))
      (node (ref "R2_3") (pin "2") (pinfunction "2_2") (pintype "passive"))
      (node (ref "R3_1") (pin "2") (pinfunction "2_2") (pintype "passive"))
    )
    (net (code "182") (name "unconnected-(3340A-CURRENT_CORR-Pad7)") (class "Default")
      (node (ref "3340A") (pin "7") (pinfunction "CURRENT_CORR_7") (pintype "bidirectional"))
    )
    (net (code "183") (name "unconnected-(3340B-CURRENT_CORR-Pad7)") (class "Default")
      (node (ref "3340B") (pin "7") (pinfunction "CURRENT_CORR_7") (pintype "bidirectional"))
    )
    (net (code "184") (name "unconnected-(CONV_ITOV_OUT-CMP-Pad5)") (class "Default")
      (node (ref "CONV_ITOV_OUT") (pin "5") (pinfunction "CMP_5") (pintype "passive"))
    )
    (net (code "185") (name "unconnected-(CONV_ITOV_OUT-ON-Pad1)") (class "Default")
      (node (ref "CONV_ITOV_OUT") (pin "1") (pinfunction "ON_1") (pintype "passive"))
    )
    (net (code "186") (name "unconnected-(CONV_ITOV_OUT-ON{slash}CMP-Pad8)") (class "Default")
      (node (ref "CONV_ITOV_OUT") (pin "8") (pinfunction "ON/CMP_8") (pintype "passive"))
    )
    (net (code "187") (name "unconnected-(IC1-GPA4-Pad25)") (class "Default")
      (node (ref "IC1") (pin "25") (pinfunction "GPA4_25") (pintype "bidirectional"))
    )
    (net (code "188") (name "unconnected-(IC1-GPA6-Pad27)") (class "Default")
      (node (ref "IC1") (pin "27") (pinfunction "GPA6_27") (pintype "bidirectional"))
    )
    (net (code "189") (name "unconnected-(IC1-GPA7-Pad28)") (class "Default")
      (node (ref "IC1") (pin "28") (pinfunction "GPA7_28") (pintype "bidirectional"))
    )
    (net (code "190") (name "unconnected-(IC1-GPB0-Pad1)") (class "Default")
      (node (ref "IC1") (pin "1") (pinfunction "GPB0_1") (pintype "bidirectional"))
    )
    (net (code "191") (name "unconnected-(IC1-GPB1-Pad2)") (class "Default")
      (node (ref "IC1") (pin "2") (pinfunction "GPB1_2") (pintype "bidirectional"))
    )
    (net (code "192") (name "unconnected-(IC1-GPB2-Pad3)") (class "Default")
      (node (ref "IC1") (pin "3") (pinfunction "GPB2_3") (pintype "bidirectional"))
    )
    (net (code "193") (name "unconnected-(IC1-GPB3-Pad4)") (class "Default")
      (node (ref "IC1") (pin "4") (pinfunction "GPB3_4") (pintype "bidirectional"))
    )
    (net (code "194") (name "unconnected-(IC1-GPB4-Pad5)") (class "Default")
      (node (ref "IC1") (pin "5") (pinfunction "GPB4_5") (pintype "bidirectional"))
    )
    (net (code "195") (name "unconnected-(IC1-INTA-Pad20)") (class "Default")
      (node (ref "IC1") (pin "20") (pinfunction "INTA_20") (pintype "output"))
    )
    (net (code "196") (name "unconnected-(IC1-INTB-Pad19)") (class "Default")
      (node (ref "IC1") (pin "19") (pinfunction "INTB_19") (pintype "output"))
    )
    (net (code "197") (name "unconnected-(JACK_SUM_STG-3-Pad2)") (class "Default")
      (node (ref "JACK_SUM_STG") (pin "2") (pinfunction "3_2") (pintype "passive"))
    )
    (net (code "198") (name "unconnected-(JP_FMLIN_VCO3340B1-Pad2)") (class "Default")
      (node (ref "JP_FMLIN_VCO3340B1") (pin "2") (pinfunction "2_2") (pintype "passive"))
    )
    (net (code "199") (name "unconnected-(JP_MIXER_B-Pad2)") (class "Default")
      (node (ref "JP_MIXER_B") (pin "2") (pinfunction "2_2") (pintype "passive"))
    )
    (net (code "200") (name "unconnected-(OPAMP_SUM_STG-CMP-Pad5)") (class "Default")
      (node (ref "OPAMP_SUM_STG") (pin "5") (pinfunction "CMP_5") (pintype "passive"))
    )
    (net (code "201") (name "unconnected-(OPAMP_SUM_STG-ON-Pad1)") (class "Default")
      (node (ref "OPAMP_SUM_STG") (pin "1") (pinfunction "ON_1") (pintype "passive"))
    )
    (net (code "202") (name "unconnected-(OPAMP_SUM_STG-ON{slash}CMP-Pad8)") (class "Default")
      (node (ref "OPAMP_SUM_STG") (pin "8") (pinfunction "ON/CMP_8") (pintype "passive"))
    )
    (net (code "203") (name "unconnected-(STM32L432KC_CONN_A-NRST-Pad3.3)") (class "Default")
      (node (ref "STM32L432KC_CONN_") (pin "3.3") (pinfunction "NRST_3.3") (pintype "bidirectional"))
    )
    (net (code "204") (name "unconnected-(STM32L432KC_CONN_A-PB1-Pad3.9)") (class "Default")
      (node (ref "STM32L432KC_CONN_") (pin "3.9") (pinfunction "PB1_3.9") (pintype "bidirectional"))
    )
    (net (code "205") (name "unconnected-(STM32L432KC_CONN_A-PF0-Pad3.10)") (class "Default")
      (node (ref "STM32L432KC_CONN_") (pin "3.10") (pinfunction "PF0_3.10") (pintype "bidirectional"))
    )
    (net (code "206") (name "unconnected-(STM32L432KC_CONN_A-PF1-Pad3.11)") (class "Default")
      (node (ref "STM32L432KC_CONN_") (pin "3.11") (pinfunction "PF1_3.11") (pintype "bidirectional"))
    )
    (net (code "207") (name "unconnected-(STM32L432KC_CONN_B-+3V3-Pad4.14)") (class "Default")
      (node (ref "STM32L432KC_CONN_") (pin "4.14") (pinfunction "+3V3_4.14") (pintype "bidirectional"))
    )
    (net (code "208") (name "unconnected-(STM32L432KC_CONN_B-+5V-Pad4.4)") (class "Default")
      (node (ref "STM32L432KC_CONN_") (pin "4.4") (pinfunction "+5V_4.4") (pintype "bidirectional"))
    )
    (net (code "209") (name "unconnected-(STM32L432KC_CONN_B-AREF-Pad4.13)") (class "Default")
      (node (ref "STM32L432KC_CONN_") (pin "4.13") (pinfunction "AREF_4.13") (pintype "bidirectional"))
    )
    (net (code "210") (name "unconnected-(STM32L432KC_CONN_B-NRST-Pad4.3)") (class "Default")
      (node (ref "STM32L432KC_CONN_") (pin "4.3") (pinfunction "NRST_4.3") (pintype "bidirectional"))
    )
    (net (code "211") (name "unconnected-(STM32L432KC_CONN_B-PA0-Pad4.12)") (class "Default")
      (node (ref "STM32L432KC_CONN_") (pin "4.12") (pinfunction "PA0_4.12") (pintype "bidirectional"))
    )
    (net (code "212") (name "unconnected-(STM32L432KC_CONN_B-PA2-Pad4.5)") (class "Default")
      (node (ref "STM32L432KC_CONN_") (pin "4.5") (pinfunction "PA2_4.5") (pintype "bidirectional"))
    )
    (net (code "213") (name "unconnected-(STM32L432KC_CONN_B-PB3-Pad4.15)") (class "Default")
      (node (ref "STM32L432KC_CONN_") (pin "4.15") (pinfunction "PB3_4.15") (pintype "bidirectional"))
    )
    (net (code "214") (name "unconnected-(SUBBASS2-2CD-Pad4)") (class "Default")
      (node (ref "SUBBASS2") (pin "4") (pinfunction "2CD_4") (pintype "input"))
    )
    (net (code "215") (name "unconnected-(SUBBASS2-2CP-Pad3)") (class "Default")
      (node (ref "SUBBASS2") (pin "3") (pinfunction "2CP_3") (pintype "input"))
    )
    (net (code "216") (name "unconnected-(SUBBASS2-2J-Pad6)") (class "Default")
      (node (ref "SUBBASS2") (pin "6") (pinfunction "2J_6") (pintype "input"))
    )
    (net (code "217") (name "unconnected-(SUBBASS2-2K-Pad5)") (class "Default")
      (node (ref "SUBBASS2") (pin "5") (pinfunction "2K_5") (pintype "input"))
    )
    (net (code "218") (name "unconnected-(SUBBASS2-2Q-Pad1)") (class "Default")
      (node (ref "SUBBASS2") (pin "1") (pinfunction "2Q_1") (pintype "output"))
    )
    (net (code "219") (name "unconnected-(SUBBASS2-2SD-Pad7)") (class "Default")
      (node (ref "SUBBASS2") (pin "7") (pinfunction "2SD_7") (pintype "input"))
    )
    (net (code "220") (name "unconnected-(SUBBASS2-2~{Q}-Pad2)") (class "Default")
      (node (ref "SUBBASS2") (pin "2") (pinfunction "2~{Q}_2") (pintype "output"))
    )
    (net (code "221") (name "unconnected-(U1A-1_NC-Pad2)") (class "Default")
      (node (ref "U1") (pin "2") (pinfunction "1_NC_2") (pintype "passive"))
    )
    (net (code "222") (name "unconnected-(U1A-2_NC-Pad3)") (class "Default")
      (node (ref "U1") (pin "3") (pinfunction "2_NC_3") (pintype "passive"))
    )
    (net (code "223") (name "unconnected-(U1A-3_NC-Pad33)") (class "Default")
      (node (ref "U1") (pin "33") (pinfunction "3_NC_33") (pintype "passive"))
    )
    (net (code "224") (name "unconnected-(U1A-4_NC-Pad34)") (class "Default")
      (node (ref "U1") (pin "34") (pinfunction "4_NC_34") (pintype "passive"))
    )
    (net (code "225") (name "unconnected-(U1A-5_NC-Pad35)") (class "Default")
      (node (ref "U1") (pin "35") (pinfunction "5_NC_35") (pintype "passive"))
    )
    (net (code "226") (name "unconnected-(U1A-6_NC-Pad36)") (class "Default")
      (node (ref "U1") (pin "36") (pinfunction "6_NC_36") (pintype "passive"))
    )
    (net (code "227") (name "unconnected-(U1A-MON_IN1-Pad18)") (class "Default")
      (node (ref "U1") (pin "18") (pinfunction "MON_IN1_18") (pintype "input"))
    )
    (net (code "228") (name "unconnected-(U1A-MON_IN2-Pad19)") (class "Default")
      (node (ref "U1") (pin "19") (pinfunction "MON_IN2_19") (pintype "input"))
    )
    (net (code "229") (name "unconnected-(U1A-MON_OUT-Pad20)") (class "Default")
      (node (ref "U1") (pin "20") (pinfunction "MON_OUT_20") (pintype "tri_state"))
    )
    (net (code "230") (name "unconnected-(VCO1C-I_DIODE-Pad2)") (class "Default")
      (node (ref "VCO1") (pin "2") (pinfunction "I_DIODE_2") (pintype "input"))
    )
    (net (code "231") (name "unconnected-(VCO2C-I_DIODE-Pad2)") (class "Default")
      (node (ref "VCO2") (pin "2") (pinfunction "I_DIODE_2") (pintype "input"))
    )
    (net (code "232") (name "unconnected-(VCO2D-I_DIODE-Pad15)") (class "Default")
      (node (ref "VCO2") (pin "15") (pinfunction "I_DIODE_15") (pintype "input"))
    )
  )
)
